# DNVT_box3.net
KiCad netlist of a schematic drawn in EAGLE
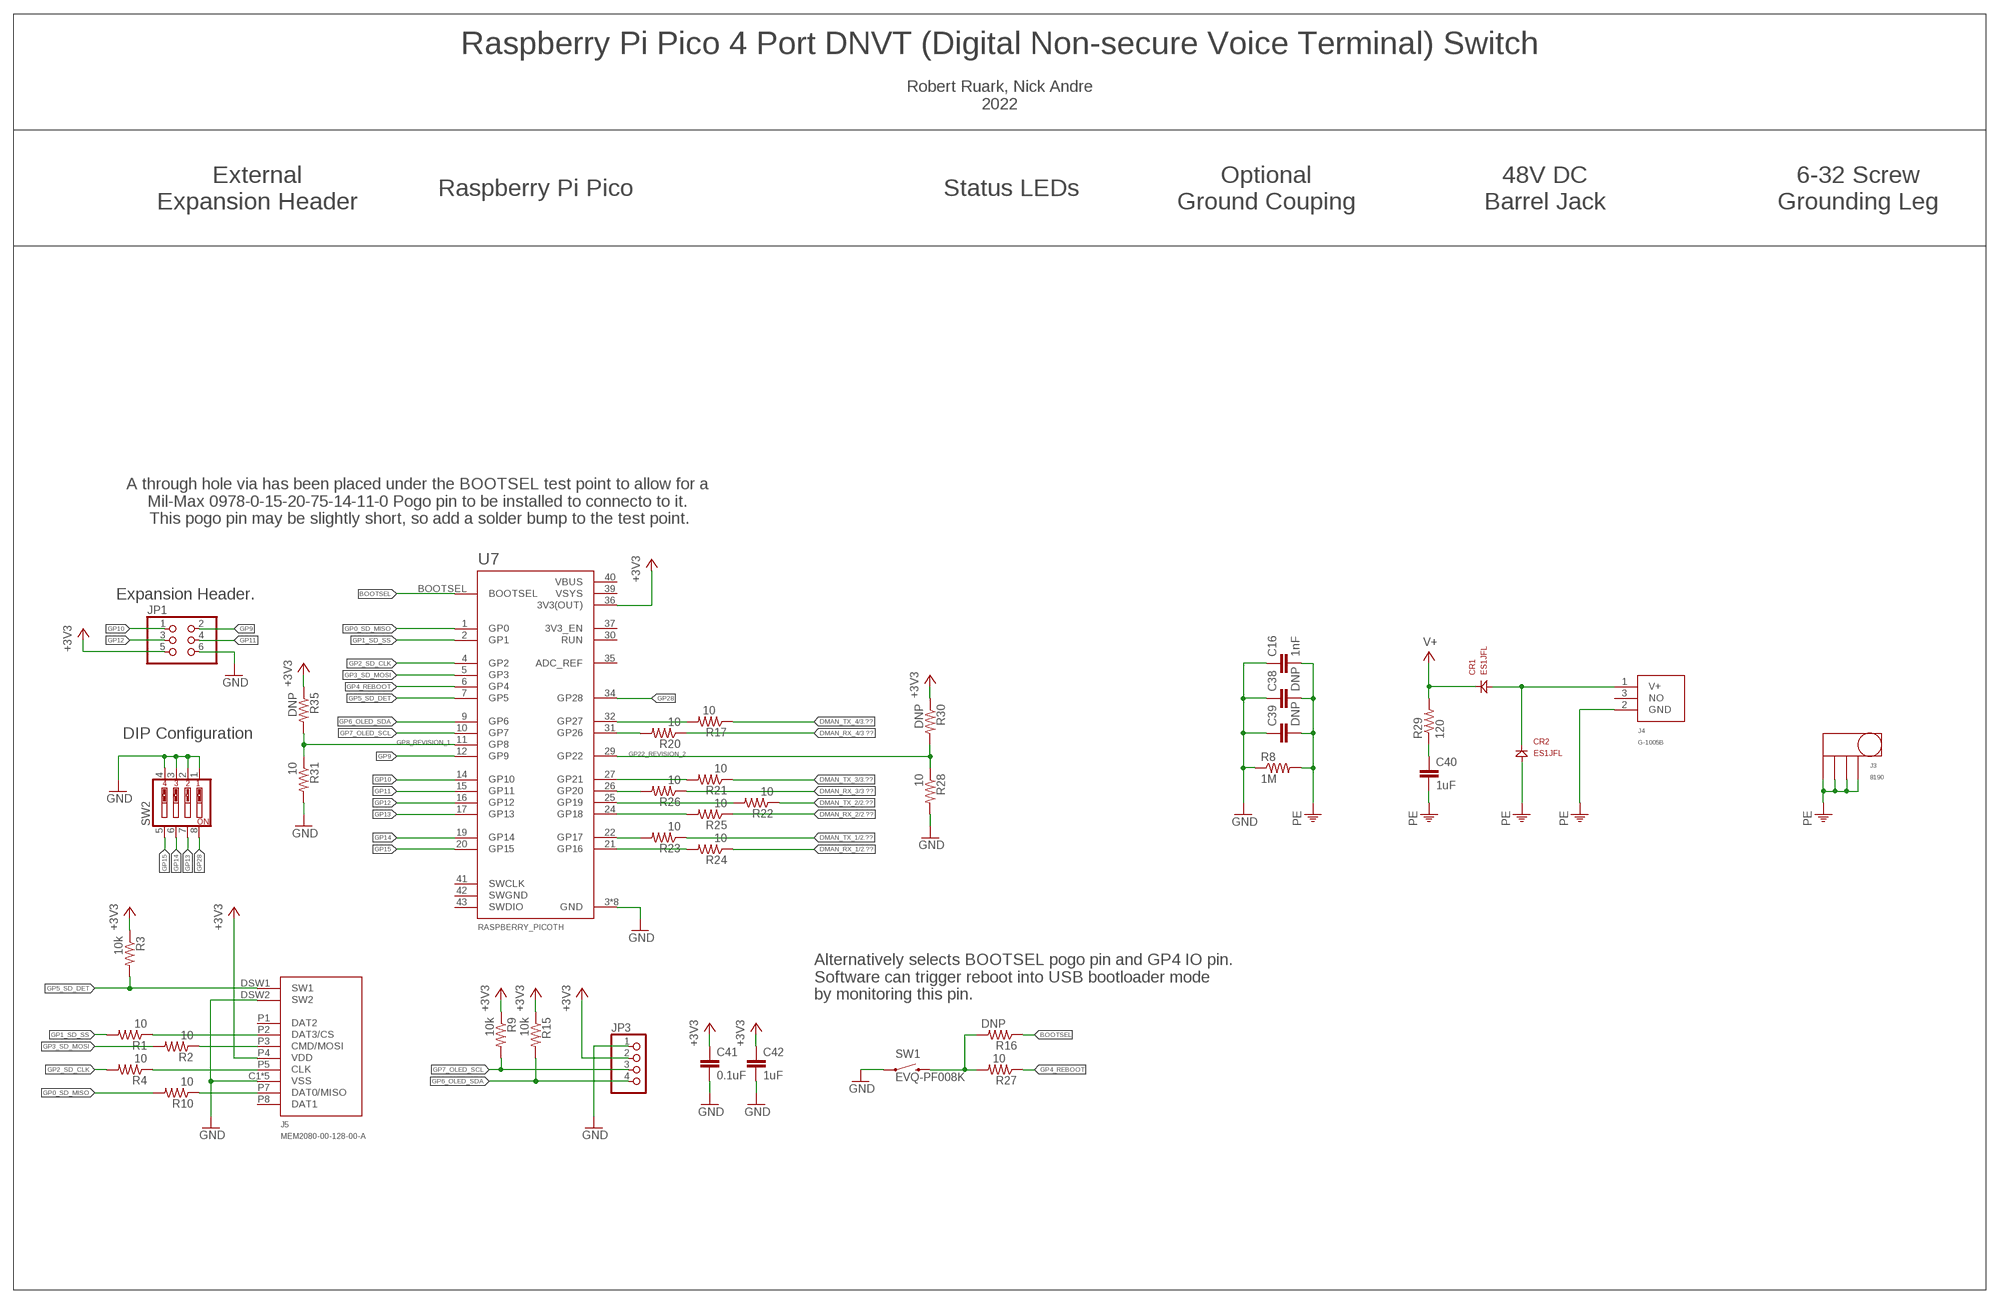
[diagram p0: schematic, sheet 1]
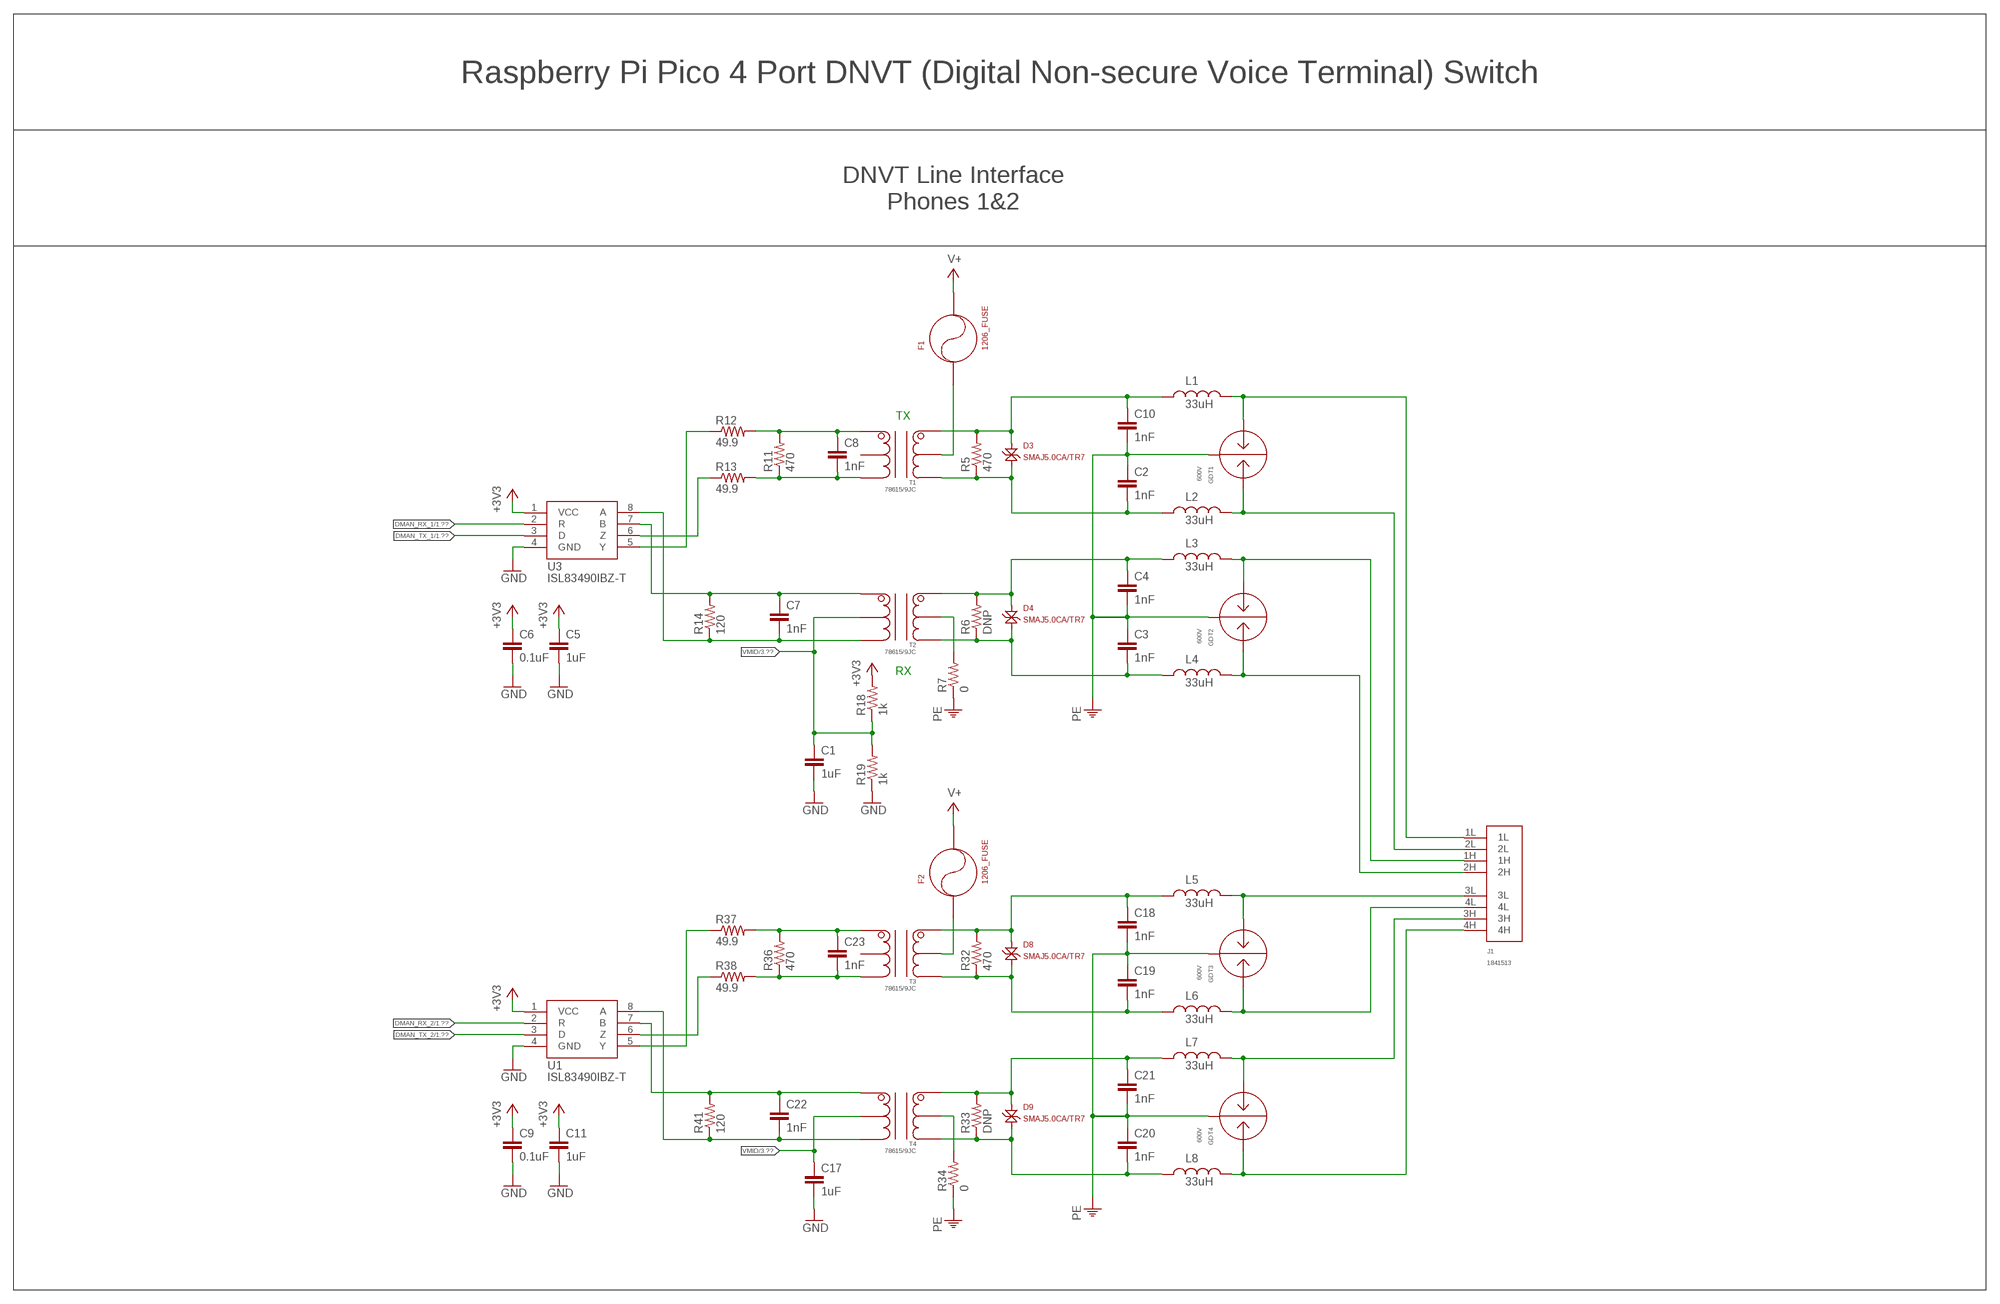
[diagram p1: schematic, sheet 2]
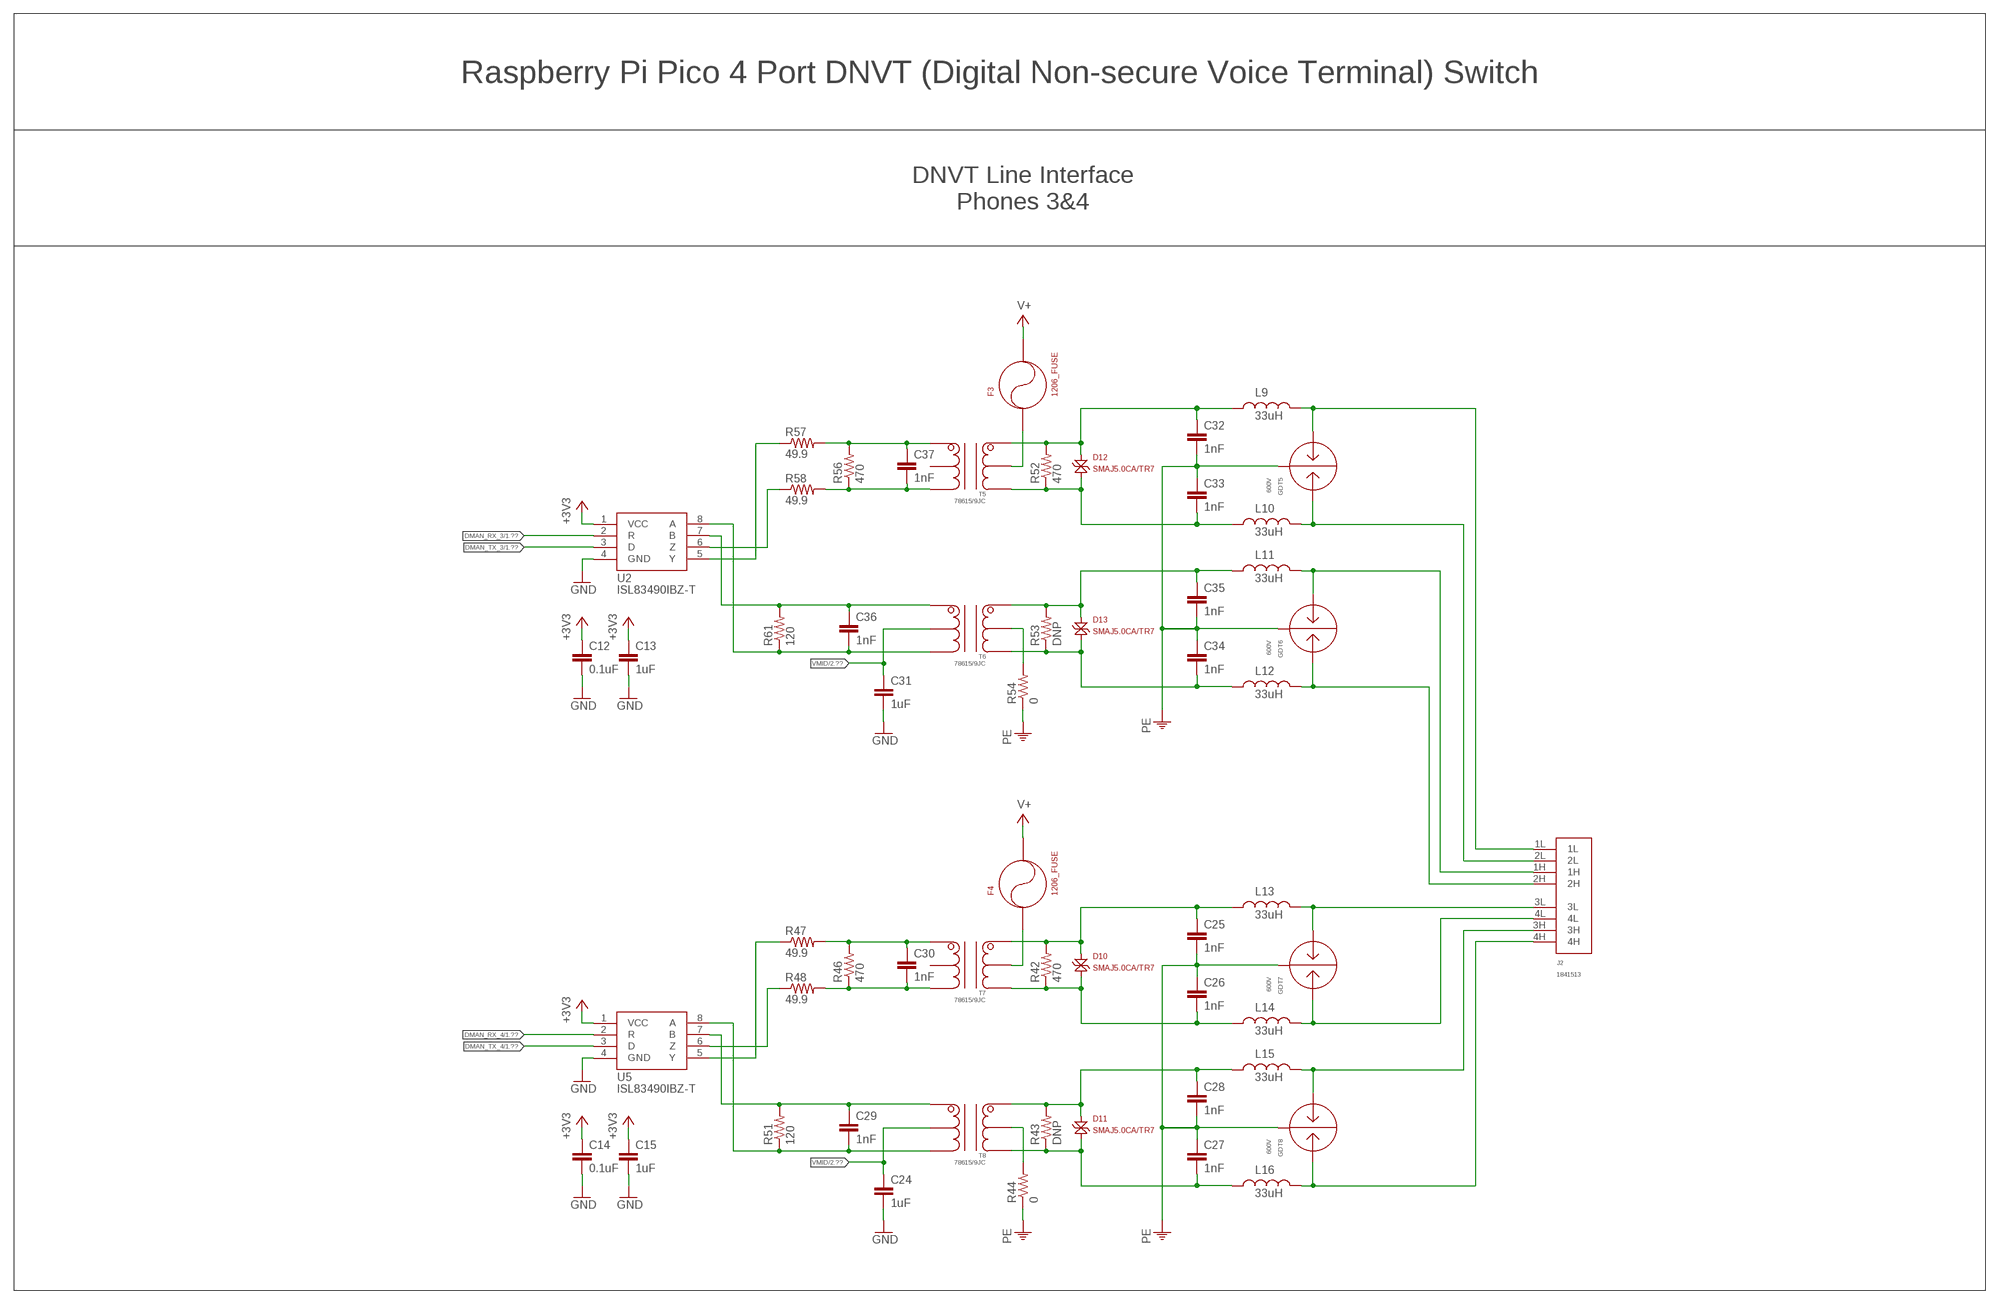
[diagram p2: schematic, sheet 3]

(export (version "E")
  (design (tool "Eeschema 10.0.6"))
  (components
    (comp (ref "C16")
      (value "1nF")
      (footprint "eagle-import:1206")
      (libsource (lib "eagle-import") (part "1206_CAPACITOR"))
    )
    (comp (ref "C38")
      (value "DNP")
      (footprint "eagle-import:1206")
      (libsource (lib "eagle-import") (part "1206_CAPACITOR"))
    )
    (comp (ref "C39")
      (value "DNP")
      (footprint "eagle-import:1206")
      (libsource (lib "eagle-import") (part "1206_CAPACITOR"))
    )
    (comp (ref "C40")
      (value "1uF")
      (footprint "eagle-import:1206")
      (libsource (lib "eagle-import") (part "1206_CAPACITOR"))
    )
    (comp (ref "C41")
      (value "0.1uF")
      (footprint "eagle-import:0603")
      (libsource (lib "eagle-import") (part "0603_CAPACITOR"))
    )
    (comp (ref "C42")
      (value "1uF")
      (footprint "eagle-import:0805")
      (libsource (lib "eagle-import") (part "0805_CAPACITOR"))
    )
    (comp (ref "CR1")
      (value "ES1JFL")
      (footprint "eagle-import:SOD123(AK)")
      (fields (field (name "PARTNO") "ES1JFLCT-ND"))
      (libsource (lib "eagle-import") (part "ES1JFL"))
    )
    (comp (ref "CR2")
      (value "ES1JFL")
      (footprint "eagle-import:SOD123(AK)")
      (fields (field (name "PARTNO") "ES1JFLCT-ND"))
      (libsource (lib "eagle-import") (part "ES1JFL"))
    )
    (comp (ref "J3")
      (value "8190")
      (footprint "eagle-import:7781")
      (fields (field (name "PARTNO") "36-8190-ND"))
      (libsource (lib "eagle-import") (part "8190"))
    )
    (comp (ref "J4")
      (value "G-1005B")
      (footprint "eagle-import:G-1005B")
      (fields (field (name "PARTNO") "1939-G-1005B-ND"))
      (libsource (lib "eagle-import") (part "G-1005B"))
    )
    (comp (ref "J5")
      (value "MEM2080-00-128-00-A")
      (footprint "eagle-import:MEM2080")
      (fields (field (name "PARTNO") "2073-MEM2080-00-128-00-ACT-ND"))
      (libsource (lib "eagle-import") (part "MEM2080-00-128-00-A"))
    )
    (comp (ref "JP1")
      (value "PINHD-2X3/90")
      (footprint "eagle-import:2X03_90")
      (libsource (lib "eagle-import") (part "PINHD-2X3/90"))
    )
    (comp (ref "JP3")
      (value "PINHD-1X4")
      (footprint "eagle-import:1X04")
      (libsource (lib "eagle-import") (part "PINHD-1X4"))
    )
    (comp (ref "R1")
      (value "10")
      (footprint "eagle-import:0603")
      (libsource (lib "eagle-import") (part "0603_RESISTOR"))
    )
    (comp (ref "R2")
      (value "10")
      (footprint "eagle-import:0603")
      (libsource (lib "eagle-import") (part "0603_RESISTOR"))
    )
    (comp (ref "R3")
      (value "10k")
      (footprint "eagle-import:0603")
      (libsource (lib "eagle-import") (part "0603_RESISTOR"))
    )
    (comp (ref "R4")
      (value "10")
      (footprint "eagle-import:0603")
      (libsource (lib "eagle-import") (part "0603_RESISTOR"))
    )
    (comp (ref "R8")
      (value "1M")
      (footprint "eagle-import:1206")
      (libsource (lib "eagle-import") (part "1206_RESISTOR"))
    )
    (comp (ref "R9")
      (value "10k")
      (footprint "eagle-import:0603")
      (libsource (lib "eagle-import") (part "0603_RESISTOR"))
    )
    (comp (ref "R10")
      (value "10")
      (footprint "eagle-import:0603")
      (libsource (lib "eagle-import") (part "0603_RESISTOR"))
    )
    (comp (ref "R15")
      (value "10k")
      (footprint "eagle-import:0603")
      (libsource (lib "eagle-import") (part "0603_RESISTOR"))
    )
    (comp (ref "R16")
      (value "DNP")
      (footprint "eagle-import:0603")
      (libsource (lib "eagle-import") (part "0603_RESISTOR"))
    )
    (comp (ref "R17")
      (value "10")
      (footprint "eagle-import:0603")
      (libsource (lib "eagle-import") (part "0603_RESISTOR"))
    )
    (comp (ref "R20")
      (value "10")
      (footprint "eagle-import:0603")
      (libsource (lib "eagle-import") (part "0603_RESISTOR"))
    )
    (comp (ref "R21")
      (value "10")
      (footprint "eagle-import:0603")
      (libsource (lib "eagle-import") (part "0603_RESISTOR"))
    )
    (comp (ref "R22")
      (value "10")
      (footprint "eagle-import:0603")
      (libsource (lib "eagle-import") (part "0603_RESISTOR"))
    )
    (comp (ref "R23")
      (value "10")
      (footprint "eagle-import:0603")
      (libsource (lib "eagle-import") (part "0603_RESISTOR"))
    )
    (comp (ref "R24")
      (value "10")
      (footprint "eagle-import:0603")
      (libsource (lib "eagle-import") (part "0603_RESISTOR"))
    )
    (comp (ref "R25")
      (value "10")
      (footprint "eagle-import:0603")
      (libsource (lib "eagle-import") (part "0603_RESISTOR"))
    )
    (comp (ref "R26")
      (value "10")
      (footprint "eagle-import:0603")
      (libsource (lib "eagle-import") (part "0603_RESISTOR"))
    )
    (comp (ref "R27")
      (value "10")
      (footprint "eagle-import:0603")
      (libsource (lib "eagle-import") (part "0603_RESISTOR"))
    )
    (comp (ref "R28")
      (value "10")
      (footprint "eagle-import:0603")
      (libsource (lib "eagle-import") (part "0603_RESISTOR"))
    )
    (comp (ref "R29")
      (value "120")
      (footprint "eagle-import:1206")
      (libsource (lib "eagle-import") (part "1206_RESISTOR"))
    )
    (comp (ref "R30")
      (value "DNP")
      (footprint "eagle-import:0603")
      (libsource (lib "eagle-import") (part "0603_RESISTOR"))
    )
    (comp (ref "R31")
      (value "10")
      (footprint "eagle-import:0603")
      (libsource (lib "eagle-import") (part "0603_RESISTOR"))
    )
    (comp (ref "R35")
      (value "DNP")
      (footprint "eagle-import:0603")
      (libsource (lib "eagle-import") (part "0603_RESISTOR"))
    )
    (comp (ref "SW1")
      (value "EVQ-PF008K")
      (footprint "eagle-import:EVQ-PF008K")
      (fields (field (name "PARTNO") "P10880S-ND"))
      (libsource (lib "eagle-import") (part "EVQ-PF008K"))
    )
    (comp (ref "SW2")
      (value "SW_DIP-4")
      (footprint "eagle-import:EDG-04")
      (libsource (lib "eagle-import") (part "SW_DIP-4"))
    )
    (comp (ref "U7")
      (value "RASPBERRY_PICOTH")
      (footprint "eagle-import:PICO-PKG-TH")
      (libsource (lib "eagle-import") (part "RASPBERRY_PICOTH"))
    )
    (comp (ref "C1")
      (value "1uF")
      (footprint "eagle-import:0805")
      (libsource (lib "eagle-import") (part "0805_CAPACITOR"))
    )
    (comp (ref "C2")
      (value "1nF")
      (footprint "eagle-import:0805")
      (libsource (lib "eagle-import") (part "0805_CAPACITOR"))
    )
    (comp (ref "C3")
      (value "1nF")
      (footprint "eagle-import:0805")
      (libsource (lib "eagle-import") (part "0805_CAPACITOR"))
    )
    (comp (ref "C4")
      (value "1nF")
      (footprint "eagle-import:0805")
      (libsource (lib "eagle-import") (part "0805_CAPACITOR"))
    )
    (comp (ref "C5")
      (value "1uF")
      (footprint "eagle-import:0805")
      (libsource (lib "eagle-import") (part "0805_CAPACITOR"))
    )
    (comp (ref "C6")
      (value "0.1uF")
      (footprint "eagle-import:0603")
      (libsource (lib "eagle-import") (part "0603_CAPACITOR"))
    )
    (comp (ref "C7")
      (value "1nF")
      (footprint "eagle-import:0805")
      (libsource (lib "eagle-import") (part "0805_CAPACITOR"))
    )
    (comp (ref "C8")
      (value "1nF")
      (footprint "eagle-import:0805")
      (libsource (lib "eagle-import") (part "0805_CAPACITOR"))
    )
    (comp (ref "C9")
      (value "0.1uF")
      (footprint "eagle-import:0603")
      (libsource (lib "eagle-import") (part "0603_CAPACITOR"))
    )
    (comp (ref "C10")
      (value "1nF")
      (footprint "eagle-import:0805")
      (libsource (lib "eagle-import") (part "0805_CAPACITOR"))
    )
    (comp (ref "C11")
      (value "1uF")
      (footprint "eagle-import:0805")
      (libsource (lib "eagle-import") (part "0805_CAPACITOR"))
    )
    (comp (ref "C17")
      (value "1uF")
      (footprint "eagle-import:0805")
      (libsource (lib "eagle-import") (part "0805_CAPACITOR"))
    )
    (comp (ref "C18")
      (value "1nF")
      (footprint "eagle-import:0805")
      (libsource (lib "eagle-import") (part "0805_CAPACITOR"))
    )
    (comp (ref "C19")
      (value "1nF")
      (footprint "eagle-import:0805")
      (libsource (lib "eagle-import") (part "0805_CAPACITOR"))
    )
    (comp (ref "C20")
      (value "1nF")
      (footprint "eagle-import:0805")
      (libsource (lib "eagle-import") (part "0805_CAPACITOR"))
    )
    (comp (ref "C21")
      (value "1nF")
      (footprint "eagle-import:0805")
      (libsource (lib "eagle-import") (part "0805_CAPACITOR"))
    )
    (comp (ref "C22")
      (value "1nF")
      (footprint "eagle-import:0805")
      (libsource (lib "eagle-import") (part "0805_CAPACITOR"))
    )
    (comp (ref "C23")
      (value "1nF")
      (footprint "eagle-import:0805")
      (libsource (lib "eagle-import") (part "0805_CAPACITOR"))
    )
    (comp (ref "D3")
      (value "SMAJ5.0CA/TR7")
      (footprint "eagle-import:DO-214AC_NO_POL")
      (libsource (lib "eagle-import") (part "SMAJ5.0CA/TR7"))
    )
    (comp (ref "D4")
      (value "SMAJ5.0CA/TR7")
      (footprint "eagle-import:DO-214AC_NO_POL")
      (libsource (lib "eagle-import") (part "SMAJ5.0CA/TR7"))
    )
    (comp (ref "D8")
      (value "SMAJ5.0CA/TR7")
      (footprint "eagle-import:DO-214AC_NO_POL")
      (libsource (lib "eagle-import") (part "SMAJ5.0CA/TR7"))
    )
    (comp (ref "D9")
      (value "SMAJ5.0CA/TR7")
      (footprint "eagle-import:DO-214AC_NO_POL")
      (libsource (lib "eagle-import") (part "SMAJ5.0CA/TR7"))
    )
    (comp (ref "F1")
      (value "1206_FUSE")
      (footprint "eagle-import:1206")
      (libsource (lib "eagle-import") (part "1206_FUSE"))
    )
    (comp (ref "F2")
      (value "1206_FUSE")
      (footprint "eagle-import:1206")
      (libsource (lib "eagle-import") (part "1206_FUSE"))
    )
    (comp (ref "GDT1")
      (value "600V")
      (footprint "eagle-import:2036_GDT")
      (fields (field (name "PARTNO") "2036-60-SM-RPLFCT-ND"))
      (libsource (lib "eagle-import") (part "2036-60-SM-RPLF"))
    )
    (comp (ref "GDT2")
      (value "600V")
      (footprint "eagle-import:2036_GDT")
      (fields (field (name "PARTNO") "2036-60-SM-RPLFCT-ND"))
      (libsource (lib "eagle-import") (part "2036-60-SM-RPLF"))
    )
    (comp (ref "GDT3")
      (value "600V")
      (footprint "eagle-import:2036_GDT")
      (fields (field (name "PARTNO") "2036-60-SM-RPLFCT-ND"))
      (libsource (lib "eagle-import") (part "2036-60-SM-RPLF"))
    )
    (comp (ref "GDT4")
      (value "600V")
      (footprint "eagle-import:2036_GDT")
      (fields (field (name "PARTNO") "2036-60-SM-RPLFCT-ND"))
      (libsource (lib "eagle-import") (part "2036-60-SM-RPLF"))
    )
    (comp (ref "J1")
      (value "1841513")
      (footprint "eagle-import:1841513")
      (fields (field (name "PARTNO") "277-10317-ND"))
      (libsource (lib "eagle-import") (part "1841513"))
    )
    (comp (ref "L1")
      (value "33uH")
      (footprint "eagle-import:SDR0403")
      (fields (field (name "PARTNO") "SDR0403-330KLCT-ND"))
      (libsource (lib "eagle-import") (part "SDR0403-330KL"))
    )
    (comp (ref "L2")
      (value "33uH")
      (footprint "eagle-import:SDR0403")
      (fields (field (name "PARTNO") "SDR0403-330KLCT-ND"))
      (libsource (lib "eagle-import") (part "SDR0403-330KL"))
    )
    (comp (ref "L3")
      (value "33uH")
      (footprint "eagle-import:SDR0403")
      (fields (field (name "PARTNO") "SDR0403-330KLCT-ND"))
      (libsource (lib "eagle-import") (part "SDR0403-330KL"))
    )
    (comp (ref "L4")
      (value "33uH")
      (footprint "eagle-import:SDR0403")
      (fields (field (name "PARTNO") "SDR0403-330KLCT-ND"))
      (libsource (lib "eagle-import") (part "SDR0403-330KL"))
    )
    (comp (ref "L5")
      (value "33uH")
      (footprint "eagle-import:SDR0403")
      (fields (field (name "PARTNO") "SDR0403-330KLCT-ND"))
      (libsource (lib "eagle-import") (part "SDR0403-330KL"))
    )
    (comp (ref "L6")
      (value "33uH")
      (footprint "eagle-import:SDR0403")
      (fields (field (name "PARTNO") "SDR0403-330KLCT-ND"))
      (libsource (lib "eagle-import") (part "SDR0403-330KL"))
    )
    (comp (ref "L7")
      (value "33uH")
      (footprint "eagle-import:SDR0403")
      (fields (field (name "PARTNO") "SDR0403-330KLCT-ND"))
      (libsource (lib "eagle-import") (part "SDR0403-330KL"))
    )
    (comp (ref "L8")
      (value "33uH")
      (footprint "eagle-import:SDR0403")
      (fields (field (name "PARTNO") "SDR0403-330KLCT-ND"))
      (libsource (lib "eagle-import") (part "SDR0403-330KL"))
    )
    (comp (ref "R5")
      (value "470")
      (footprint "eagle-import:R0805")
      (libsource (lib "eagle-import") (part "R-US_R0805"))
    )
    (comp (ref "R6")
      (value "DNP")
      (footprint "eagle-import:R0805")
      (libsource (lib "eagle-import") (part "R-US_R0805"))
    )
    (comp (ref "R7")
      (value "0")
      (footprint "eagle-import:R0805")
      (libsource (lib "eagle-import") (part "R-US_R0805"))
    )
    (comp (ref "R11")
      (value "470")
      (footprint "eagle-import:R0805")
      (libsource (lib "eagle-import") (part "R-US_R0805"))
    )
    (comp (ref "R12")
      (value "49.9")
      (footprint "eagle-import:R0805")
      (libsource (lib "eagle-import") (part "R-US_R0805"))
    )
    (comp (ref "R13")
      (value "49.9")
      (footprint "eagle-import:R0805")
      (libsource (lib "eagle-import") (part "R-US_R0805"))
    )
    (comp (ref "R14")
      (value "120")
      (footprint "eagle-import:1206")
      (libsource (lib "eagle-import") (part "1206_RESISTOR"))
    )
    (comp (ref "R18")
      (value "1k")
      (footprint "eagle-import:0603")
      (libsource (lib "eagle-import") (part "0603_RESISTOR"))
    )
    (comp (ref "R19")
      (value "1k")
      (footprint "eagle-import:0603")
      (libsource (lib "eagle-import") (part "0603_RESISTOR"))
    )
    (comp (ref "R32")
      (value "470")
      (footprint "eagle-import:R0805")
      (libsource (lib "eagle-import") (part "R-US_R0805"))
    )
    (comp (ref "R33")
      (value "DNP")
      (footprint "eagle-import:R0805")
      (libsource (lib "eagle-import") (part "R-US_R0805"))
    )
    (comp (ref "R34")
      (value "0")
      (footprint "eagle-import:R0805")
      (libsource (lib "eagle-import") (part "R-US_R0805"))
    )
    (comp (ref "R36")
      (value "470")
      (footprint "eagle-import:R0805")
      (libsource (lib "eagle-import") (part "R-US_R0805"))
    )
    (comp (ref "R37")
      (value "49.9")
      (footprint "eagle-import:R0805")
      (libsource (lib "eagle-import") (part "R-US_R0805"))
    )
    (comp (ref "R38")
      (value "49.9")
      (footprint "eagle-import:R0805")
      (libsource (lib "eagle-import") (part "R-US_R0805"))
    )
    (comp (ref "R41")
      (value "120")
      (footprint "eagle-import:1206")
      (libsource (lib "eagle-import") (part "1206_RESISTOR"))
    )
    (comp (ref "T1")
      (value "78615/9JC")
      (footprint "eagle-import:786")
      (fields (field (name "PARTNO") "811-2423-ND"))
      (libsource (lib "eagle-import") (part "78615/9JC"))
    )
    (comp (ref "T2")
      (value "78615/9JC")
      (footprint "eagle-import:786")
      (fields (field (name "PARTNO") "811-2423-ND"))
      (libsource (lib "eagle-import") (part "78615/9JC"))
    )
    (comp (ref "T3")
      (value "78615/9JC")
      (footprint "eagle-import:786")
      (fields (field (name "PARTNO") "811-2423-ND"))
      (libsource (lib "eagle-import") (part "78615/9JC"))
    )
    (comp (ref "T4")
      (value "78615/9JC")
      (footprint "eagle-import:786")
      (fields (field (name "PARTNO") "811-2423-ND"))
      (libsource (lib "eagle-import") (part "78615/9JC"))
    )
    (comp (ref "U1")
      (value "ISL83490IBZ-T")
      (footprint "eagle-import:SOIC8")
      (fields (field (name "PARTNO") "ISL83490IBZ-TCT-ND"))
      (libsource (lib "eagle-import") (part "ISL83490IBZ-T"))
    )
    (comp (ref "U3")
      (value "ISL83490IBZ-T")
      (footprint "eagle-import:SOIC8")
      (fields (field (name "PARTNO") "ISL83490IBZ-TCT-ND"))
      (libsource (lib "eagle-import") (part "ISL83490IBZ-T"))
    )
    (comp (ref "C12")
      (value "0.1uF")
      (footprint "eagle-import:0603")
      (libsource (lib "eagle-import") (part "0603_CAPACITOR"))
    )
    (comp (ref "C13")
      (value "1uF")
      (footprint "eagle-import:0805")
      (libsource (lib "eagle-import") (part "0805_CAPACITOR"))
    )
    (comp (ref "C14")
      (value "0.1uF")
      (footprint "eagle-import:0603")
      (libsource (lib "eagle-import") (part "0603_CAPACITOR"))
    )
    (comp (ref "C15")
      (value "1uF")
      (footprint "eagle-import:0805")
      (libsource (lib "eagle-import") (part "0805_CAPACITOR"))
    )
    (comp (ref "C24")
      (value "1uF")
      (footprint "eagle-import:0805")
      (libsource (lib "eagle-import") (part "0805_CAPACITOR"))
    )
    (comp (ref "C25")
      (value "1nF")
      (footprint "eagle-import:0805")
      (libsource (lib "eagle-import") (part "0805_CAPACITOR"))
    )
    (comp (ref "C26")
      (value "1nF")
      (footprint "eagle-import:0805")
      (libsource (lib "eagle-import") (part "0805_CAPACITOR"))
    )
    (comp (ref "C27")
      (value "1nF")
      (footprint "eagle-import:0805")
      (libsource (lib "eagle-import") (part "0805_CAPACITOR"))
    )
    (comp (ref "C28")
      (value "1nF")
      (footprint "eagle-import:0805")
      (libsource (lib "eagle-import") (part "0805_CAPACITOR"))
    )
    (comp (ref "C29")
      (value "1nF")
      (footprint "eagle-import:0805")
      (libsource (lib "eagle-import") (part "0805_CAPACITOR"))
    )
    (comp (ref "C30")
      (value "1nF")
      (footprint "eagle-import:0805")
      (libsource (lib "eagle-import") (part "0805_CAPACITOR"))
    )
    (comp (ref "C31")
      (value "1uF")
      (footprint "eagle-import:0805")
      (libsource (lib "eagle-import") (part "0805_CAPACITOR"))
    )
    (comp (ref "C32")
      (value "1nF")
      (footprint "eagle-import:0805")
      (libsource (lib "eagle-import") (part "0805_CAPACITOR"))
    )
    (comp (ref "C33")
      (value "1nF")
      (footprint "eagle-import:0805")
      (libsource (lib "eagle-import") (part "0805_CAPACITOR"))
    )
    (comp (ref "C34")
      (value "1nF")
      (footprint "eagle-import:0805")
      (libsource (lib "eagle-import") (part "0805_CAPACITOR"))
    )
    (comp (ref "C35")
      (value "1nF")
      (footprint "eagle-import:0805")
      (libsource (lib "eagle-import") (part "0805_CAPACITOR"))
    )
    (comp (ref "C36")
      (value "1nF")
      (footprint "eagle-import:0805")
      (libsource (lib "eagle-import") (part "0805_CAPACITOR"))
    )
    (comp (ref "C37")
      (value "1nF")
      (footprint "eagle-import:0805")
      (libsource (lib "eagle-import") (part "0805_CAPACITOR"))
    )
    (comp (ref "D10")
      (value "SMAJ5.0CA/TR7")
      (footprint "eagle-import:DO-214AC_NO_POL")
      (libsource (lib "eagle-import") (part "SMAJ5.0CA/TR7"))
    )
    (comp (ref "D11")
      (value "SMAJ5.0CA/TR7")
      (footprint "eagle-import:DO-214AC_NO_POL")
      (libsource (lib "eagle-import") (part "SMAJ5.0CA/TR7"))
    )
    (comp (ref "D12")
      (value "SMAJ5.0CA/TR7")
      (footprint "eagle-import:DO-214AC_NO_POL")
      (libsource (lib "eagle-import") (part "SMAJ5.0CA/TR7"))
    )
    (comp (ref "D13")
      (value "SMAJ5.0CA/TR7")
      (footprint "eagle-import:DO-214AC_NO_POL")
      (libsource (lib "eagle-import") (part "SMAJ5.0CA/TR7"))
    )
    (comp (ref "F3")
      (value "1206_FUSE")
      (footprint "eagle-import:1206")
      (libsource (lib "eagle-import") (part "1206_FUSE"))
    )
    (comp (ref "F4")
      (value "1206_FUSE")
      (footprint "eagle-import:1206")
      (libsource (lib "eagle-import") (part "1206_FUSE"))
    )
    (comp (ref "GDT5")
      (value "600V")
      (footprint "eagle-import:2036_GDT")
      (fields (field (name "PARTNO") "2036-60-SM-RPLFCT-ND"))
      (libsource (lib "eagle-import") (part "2036-60-SM-RPLF"))
    )
    (comp (ref "GDT6")
      (value "600V")
      (footprint "eagle-import:2036_GDT")
      (fields (field (name "PARTNO") "2036-60-SM-RPLFCT-ND"))
      (libsource (lib "eagle-import") (part "2036-60-SM-RPLF"))
    )
    (comp (ref "GDT7")
      (value "600V")
      (footprint "eagle-import:2036_GDT")
      (fields (field (name "PARTNO") "2036-60-SM-RPLFCT-ND"))
      (libsource (lib "eagle-import") (part "2036-60-SM-RPLF"))
    )
    (comp (ref "GDT8")
      (value "600V")
      (footprint "eagle-import:2036_GDT")
      (fields (field (name "PARTNO") "2036-60-SM-RPLFCT-ND"))
      (libsource (lib "eagle-import") (part "2036-60-SM-RPLF"))
    )
    (comp (ref "J2")
      (value "1841513")
      (footprint "eagle-import:1841513")
      (fields (field (name "PARTNO") "277-10317-ND"))
      (libsource (lib "eagle-import") (part "1841513"))
    )
    (comp (ref "L9")
      (value "33uH")
      (footprint "eagle-import:SDR0403")
      (fields (field (name "PARTNO") "SDR0403-330KLCT-ND"))
      (libsource (lib "eagle-import") (part "SDR0403-330KL"))
    )
    (comp (ref "L10")
      (value "33uH")
      (footprint "eagle-import:SDR0403")
      (fields (field (name "PARTNO") "SDR0403-330KLCT-ND"))
      (libsource (lib "eagle-import") (part "SDR0403-330KL"))
    )
    (comp (ref "L11")
      (value "33uH")
      (footprint "eagle-import:SDR0403")
      (fields (field (name "PARTNO") "SDR0403-330KLCT-ND"))
      (libsource (lib "eagle-import") (part "SDR0403-330KL"))
    )
    (comp (ref "L12")
      (value "33uH")
      (footprint "eagle-import:SDR0403")
      (fields (field (name "PARTNO") "SDR0403-330KLCT-ND"))
      (libsource (lib "eagle-import") (part "SDR0403-330KL"))
    )
    (comp (ref "L13")
      (value "33uH")
      (footprint "eagle-import:SDR0403")
      (fields (field (name "PARTNO") "SDR0403-330KLCT-ND"))
      (libsource (lib "eagle-import") (part "SDR0403-330KL"))
    )
    (comp (ref "L14")
      (value "33uH")
      (footprint "eagle-import:SDR0403")
      (fields (field (name "PARTNO") "SDR0403-330KLCT-ND"))
      (libsource (lib "eagle-import") (part "SDR0403-330KL"))
    )
    (comp (ref "L15")
      (value "33uH")
      (footprint "eagle-import:SDR0403")
      (fields (field (name "PARTNO") "SDR0403-330KLCT-ND"))
      (libsource (lib "eagle-import") (part "SDR0403-330KL"))
    )
    (comp (ref "L16")
      (value "33uH")
      (footprint "eagle-import:SDR0403")
      (fields (field (name "PARTNO") "SDR0403-330KLCT-ND"))
      (libsource (lib "eagle-import") (part "SDR0403-330KL"))
    )
    (comp (ref "R42")
      (value "470")
      (footprint "eagle-import:R0805")
      (libsource (lib "eagle-import") (part "R-US_R0805"))
    )
    (comp (ref "R43")
      (value "DNP")
      (footprint "eagle-import:R0805")
      (libsource (lib "eagle-import") (part "R-US_R0805"))
    )
    (comp (ref "R44")
      (value "0")
      (footprint "eagle-import:R0805")
      (libsource (lib "eagle-import") (part "R-US_R0805"))
    )
    (comp (ref "R46")
      (value "470")
      (footprint "eagle-import:R0805")
      (libsource (lib "eagle-import") (part "R-US_R0805"))
    )
    (comp (ref "R47")
      (value "49.9")
      (footprint "eagle-import:R0805")
      (libsource (lib "eagle-import") (part "R-US_R0805"))
    )
    (comp (ref "R48")
      (value "49.9")
      (footprint "eagle-import:R0805")
      (libsource (lib "eagle-import") (part "R-US_R0805"))
    )
    (comp (ref "R51")
      (value "120")
      (footprint "eagle-import:1206")
      (libsource (lib "eagle-import") (part "1206_RESISTOR"))
    )
    (comp (ref "R52")
      (value "470")
      (footprint "eagle-import:R0805")
      (libsource (lib "eagle-import") (part "R-US_R0805"))
    )
    (comp (ref "R53")
      (value "DNP")
      (footprint "eagle-import:R0805")
      (libsource (lib "eagle-import") (part "R-US_R0805"))
    )
    (comp (ref "R54")
      (value "0")
      (footprint "eagle-import:R0805")
      (libsource (lib "eagle-import") (part "R-US_R0805"))
    )
    (comp (ref "R56")
      (value "470")
      (footprint "eagle-import:R0805")
      (libsource (lib "eagle-import") (part "R-US_R0805"))
    )
    (comp (ref "R57")
      (value "49.9")
      (footprint "eagle-import:R0805")
      (libsource (lib "eagle-import") (part "R-US_R0805"))
    )
    (comp (ref "R58")
      (value "49.9")
      (footprint "eagle-import:R0805")
      (libsource (lib "eagle-import") (part "R-US_R0805"))
    )
    (comp (ref "R61")
      (value "120")
      (footprint "eagle-import:1206")
      (libsource (lib "eagle-import") (part "1206_RESISTOR"))
    )
    (comp (ref "T5")
      (value "78615/9JC")
      (footprint "eagle-import:786")
      (fields (field (name "PARTNO") "811-2423-ND"))
      (libsource (lib "eagle-import") (part "78615/9JC"))
    )
    (comp (ref "T6")
      (value "78615/9JC")
      (footprint "eagle-import:786")
      (fields (field (name "PARTNO") "811-2423-ND"))
      (libsource (lib "eagle-import") (part "78615/9JC"))
    )
    (comp (ref "T7")
      (value "78615/9JC")
      (footprint "eagle-import:786")
      (fields (field (name "PARTNO") "811-2423-ND"))
      (libsource (lib "eagle-import") (part "78615/9JC"))
    )
    (comp (ref "T8")
      (value "78615/9JC")
      (footprint "eagle-import:786")
      (fields (field (name "PARTNO") "811-2423-ND"))
      (libsource (lib "eagle-import") (part "78615/9JC"))
    )
    (comp (ref "U2")
      (value "ISL83490IBZ-T")
      (footprint "eagle-import:SOIC8")
      (fields (field (name "PARTNO") "ISL83490IBZ-TCT-ND"))
      (libsource (lib "eagle-import") (part "ISL83490IBZ-T"))
    )
    (comp (ref "U5")
      (value "ISL83490IBZ-T")
      (footprint "eagle-import:SOIC8")
      (fields (field (name "PARTNO") "ISL83490IBZ-TCT-ND"))
      (libsource (lib "eagle-import") (part "ISL83490IBZ-T"))
    )
  )
  (nets
    (net (code "1") (name "+3V3") (class "Default")
      (node (ref "C11") (pin "1") (pinfunction "1_1") (pintype "passive"))
      (node (ref "C12") (pin "1") (pinfunction "1_1") (pintype "passive"))
      (node (ref "C13") (pin "1") (pinfunction "1_1") (pintype "passive"))
      (node (ref "C14") (pin "1") (pinfunction "1_1") (pintype "passive"))
      (node (ref "C15") (pin "1") (pinfunction "1_1") (pintype "passive"))
      (node (ref "C41") (pin "1") (pinfunction "1_1") (pintype "passive"))
      (node (ref "C42") (pin "1") (pinfunction "1_1") (pintype "passive"))
      (node (ref "C5") (pin "1") (pinfunction "1_1") (pintype "passive"))
      (node (ref "C6") (pin "1") (pinfunction "1_1") (pintype "passive"))
      (node (ref "C9") (pin "1") (pinfunction "1_1") (pintype "passive"))
      (node (ref "J5") (pin "P4") (pinfunction "VDD_P4") (pintype "bidirectional"))
      (node (ref "JP1") (pin "5") (pinfunction "5_5") (pintype "passive"))
      (node (ref "JP3") (pin "2") (pinfunction "2_2") (pintype "passive"))
      (node (ref "R15") (pin "1") (pinfunction "1_1") (pintype "passive"))
      (node (ref "R18") (pin "2") (pinfunction "2_2") (pintype "passive"))
      (node (ref "R3") (pin "1") (pinfunction "1_1") (pintype "passive"))
      (node (ref "R30") (pin "1") (pinfunction "1_1") (pintype "passive"))
      (node (ref "R35") (pin "1") (pinfunction "1_1") (pintype "passive"))
      (node (ref "R9") (pin "1") (pinfunction "1_1") (pintype "passive"))
      (node (ref "U1") (pin "1") (pinfunction "VCC_1") (pintype "bidirectional"))
      (node (ref "U2") (pin "1") (pinfunction "VCC_1") (pintype "bidirectional"))
      (node (ref "U3") (pin "1") (pinfunction "VCC_1") (pintype "bidirectional"))
      (node (ref "U5") (pin "1") (pinfunction "VCC_1") (pintype "bidirectional"))
      (node (ref "U7") (pin "36") (pinfunction "3V3(OUT)_36") (pintype "power_in"))
    )
    (net (code "2") (name "BOOTSEL") (class "Default")
      (node (ref "R16") (pin "1") (pinfunction "1_1") (pintype "passive"))
      (node (ref "U7") (pin "BOOTSEL") (pinfunction "BOOTSEL_BOOTSEL") (pintype "bidirectional"))
    )
    (net (code "3") (name "DMAN_RX_1") (class "Default")
      (node (ref "R24") (pin "1") (pinfunction "1_1") (pintype "passive"))
      (node (ref "U3") (pin "2") (pinfunction "R_2") (pintype "bidirectional"))
    )
    (net (code "4") (name "DMAN_RX_2") (class "Default")
      (node (ref "R25") (pin "1") (pinfunction "1_1") (pintype "passive"))
      (node (ref "U1") (pin "2") (pinfunction "R_2") (pintype "bidirectional"))
    )
    (net (code "5") (name "DMAN_RX_3") (class "Default")
      (node (ref "R26") (pin "1") (pinfunction "1_1") (pintype "passive"))
      (node (ref "U2") (pin "2") (pinfunction "R_2") (pintype "bidirectional"))
    )
    (net (code "6") (name "DMAN_RX_4") (class "Default")
      (node (ref "R20") (pin "1") (pinfunction "1_1") (pintype "passive"))
      (node (ref "U5") (pin "2") (pinfunction "R_2") (pintype "bidirectional"))
    )
    (net (code "7") (name "DMAN_TX_1") (class "Default")
      (node (ref "R23") (pin "1") (pinfunction "1_1") (pintype "passive"))
      (node (ref "U3") (pin "3") (pinfunction "D_3") (pintype "bidirectional"))
    )
    (net (code "8") (name "DMAN_TX_2") (class "Default")
      (node (ref "R22") (pin "1") (pinfunction "1_1") (pintype "passive"))
      (node (ref "U1") (pin "3") (pinfunction "D_3") (pintype "bidirectional"))
    )
    (net (code "9") (name "DMAN_TX_3") (class "Default")
      (node (ref "R21") (pin "1") (pinfunction "1_1") (pintype "passive"))
      (node (ref "U2") (pin "3") (pinfunction "D_3") (pintype "bidirectional"))
    )
    (net (code "10") (name "DMAN_TX_4") (class "Default")
      (node (ref "R17") (pin "1") (pinfunction "1_1") (pintype "passive"))
      (node (ref "U5") (pin "3") (pinfunction "D_3") (pintype "bidirectional"))
    )
    (net (code "11") (name "GND") (class "Default")
      (node (ref "C1") (pin "2") (pinfunction "2_2") (pintype "passive"))
      (node (ref "C11") (pin "2") (pinfunction "2_2") (pintype "passive"))
      (node (ref "C12") (pin "2") (pinfunction "2_2") (pintype "passive"))
      (node (ref "C13") (pin "2") (pinfunction "2_2") (pintype "passive"))
      (node (ref "C14") (pin "2") (pinfunction "2_2") (pintype "passive"))
      (node (ref "C15") (pin "2") (pinfunction "2_2") (pintype "passive"))
      (node (ref "C16") (pin "1") (pinfunction "1_1") (pintype "passive"))
      (node (ref "C17") (pin "2") (pinfunction "2_2") (pintype "passive"))
      (node (ref "C24") (pin "2") (pinfunction "2_2") (pintype "passive"))
      (node (ref "C31") (pin "2") (pinfunction "2_2") (pintype "passive"))
      (node (ref "C38") (pin "1") (pinfunction "1_1") (pintype "passive"))
      (node (ref "C39") (pin "1") (pinfunction "1_1") (pintype "passive"))
      (node (ref "C41") (pin "2") (pinfunction "2_2") (pintype "passive"))
      (node (ref "C42") (pin "2") (pinfunction "2_2") (pintype "passive"))
      (node (ref "C5") (pin "2") (pinfunction "2_2") (pintype "passive"))
      (node (ref "C6") (pin "2") (pinfunction "2_2") (pintype "passive"))
      (node (ref "C9") (pin "2") (pinfunction "2_2") (pintype "passive"))
      (node (ref "J5") (pin "C1") (pinfunction "VSS_C1") (pintype "bidirectional"))
      (node (ref "J5") (pin "C2") (pinfunction "VSS_C2") (pintype "bidirectional"))
      (node (ref "J5") (pin "C3") (pinfunction "VSS_C3") (pintype "bidirectional"))
      (node (ref "J5") (pin "C4") (pinfunction "VSS_C4") (pintype "bidirectional"))
      (node (ref "J5") (pin "DSW2") (pinfunction "SW2_DSW2") (pintype "bidirectional"))
      (node (ref "J5") (pin "P6") (pinfunction "VSS_P6") (pintype "bidirectional"))
      (node (ref "JP1") (pin "6") (pinfunction "6_6") (pintype "passive"))
      (node (ref "JP3") (pin "1") (pinfunction "1_1") (pintype "passive"))
      (node (ref "R19") (pin "1") (pinfunction "1_1") (pintype "passive"))
      (node (ref "R28") (pin "2") (pinfunction "2_2") (pintype "passive"))
      (node (ref "R31") (pin "2") (pinfunction "2_2") (pintype "passive"))
      (node (ref "R8") (pin "1") (pinfunction "1_1") (pintype "passive"))
      (node (ref "SW1") (pin "S1") (pinfunction "1_S1") (pintype "passive"))
      (node (ref "SW2") (pin "1") (pinfunction "1_1") (pintype "passive"))
      (node (ref "SW2") (pin "2") (pinfunction "2_2") (pintype "passive"))
      (node (ref "SW2") (pin "3") (pinfunction "3_3") (pintype "passive"))
      (node (ref "SW2") (pin "4") (pinfunction "4_4") (pintype "passive"))
      (node (ref "U1") (pin "4") (pinfunction "GND_4") (pintype "bidirectional"))
      (node (ref "U2") (pin "4") (pinfunction "GND_4") (pintype "bidirectional"))
      (node (ref "U3") (pin "4") (pinfunction "GND_4") (pintype "bidirectional"))
      (node (ref "U5") (pin "4") (pinfunction "GND_4") (pintype "bidirectional"))
      (node (ref "U7") (pin "13") (pinfunction "GND_13") (pintype "power_in"))
      (node (ref "U7") (pin "18") (pinfunction "GND_18") (pintype "power_in"))
      (node (ref "U7") (pin "23") (pinfunction "GND_23") (pintype "power_in"))
      (node (ref "U7") (pin "28") (pinfunction "GND_28") (pintype "power_in"))
      (node (ref "U7") (pin "3") (pinfunction "GND_3") (pintype "power_in"))
      (node (ref "U7") (pin "33") (pinfunction "GND_33") (pintype "power_in"))
      (node (ref "U7") (pin "38") (pinfunction "GND_38") (pintype "power_in"))
      (node (ref "U7") (pin "8") (pinfunction "GND_8") (pintype "power_in"))
    )
    (net (code "12") (name "GP0_SD_MISO") (class "Default")
      (node (ref "R10") (pin "2") (pinfunction "2_2") (pintype "passive"))
      (node (ref "U7") (pin "1") (pinfunction "GP0_1") (pintype "bidirectional"))
    )
    (net (code "13") (name "GP1_SD_SS") (class "Default")
      (node (ref "R1") (pin "2") (pinfunction "2_2") (pintype "passive"))
      (node (ref "U7") (pin "2") (pinfunction "GP1_2") (pintype "bidirectional"))
    )
    (net (code "14") (name "GP2_SD_CLK") (class "Default")
      (node (ref "R4") (pin "2") (pinfunction "2_2") (pintype "passive"))
      (node (ref "U7") (pin "4") (pinfunction "GP2_4") (pintype "bidirectional"))
    )
    (net (code "15") (name "GP3_SD_MOSI") (class "Default")
      (node (ref "R2") (pin "2") (pinfunction "2_2") (pintype "passive"))
      (node (ref "U7") (pin "5") (pinfunction "GP3_5") (pintype "bidirectional"))
    )
    (net (code "16") (name "GP4_REBOOT") (class "Default")
      (node (ref "R27") (pin "1") (pinfunction "1_1") (pintype "passive"))
      (node (ref "U7") (pin "6") (pinfunction "GP4_6") (pintype "bidirectional"))
    )
    (net (code "17") (name "GP5_SD_DET") (class "Default")
      (node (ref "J5") (pin "DSW1") (pinfunction "SW1_DSW1") (pintype "bidirectional"))
      (node (ref "R3") (pin "2") (pinfunction "2_2") (pintype "passive"))
      (node (ref "U7") (pin "7") (pinfunction "GP5_7") (pintype "bidirectional"))
    )
    (net (code "18") (name "GP6_OLED_SDA") (class "Default")
      (node (ref "JP3") (pin "4") (pinfunction "4_4") (pintype "passive"))
      (node (ref "R15") (pin "2") (pinfunction "2_2") (pintype "passive"))
      (node (ref "U7") (pin "9") (pinfunction "GP6_9") (pintype "bidirectional"))
    )
    (net (code "19") (name "GP7_OLED_SCL") (class "Default")
      (node (ref "JP3") (pin "3") (pinfunction "3_3") (pintype "passive"))
      (node (ref "R9") (pin "2") (pinfunction "2_2") (pintype "passive"))
      (node (ref "U7") (pin "10") (pinfunction "GP7_10") (pintype "bidirectional"))
    )
    (net (code "20") (name "GP8_REVISION_1") (class "Default")
      (node (ref "R31") (pin "1") (pinfunction "1_1") (pintype "passive"))
      (node (ref "R35") (pin "2") (pinfunction "2_2") (pintype "passive"))
      (node (ref "U7") (pin "11") (pinfunction "GP8_11") (pintype "bidirectional"))
    )
    (net (code "21") (name "GP9") (class "Default")
      (node (ref "JP1") (pin "2") (pinfunction "2_2") (pintype "passive"))
      (node (ref "U7") (pin "12") (pinfunction "GP9_12") (pintype "bidirectional"))
    )
    (net (code "22") (name "GP10") (class "Default")
      (node (ref "JP1") (pin "1") (pinfunction "1_1") (pintype "passive"))
      (node (ref "U7") (pin "14") (pinfunction "GP10_14") (pintype "bidirectional"))
    )
    (net (code "23") (name "GP11") (class "Default")
      (node (ref "JP1") (pin "4") (pinfunction "4_4") (pintype "passive"))
      (node (ref "U7") (pin "15") (pinfunction "GP11_15") (pintype "bidirectional"))
    )
    (net (code "24") (name "GP12") (class "Default")
      (node (ref "JP1") (pin "3") (pinfunction "3_3") (pintype "passive"))
      (node (ref "U7") (pin "16") (pinfunction "GP12_16") (pintype "bidirectional"))
    )
    (net (code "25") (name "GP13") (class "Default")
      (node (ref "SW2") (pin "7") (pinfunction "7_7") (pintype "passive"))
      (node (ref "U7") (pin "17") (pinfunction "GP13_17") (pintype "bidirectional"))
    )
    (net (code "26") (name "GP14") (class "Default")
      (node (ref "SW2") (pin "6") (pinfunction "6_6") (pintype "passive"))
      (node (ref "U7") (pin "19") (pinfunction "GP14_19") (pintype "bidirectional"))
    )
    (net (code "27") (name "GP15") (class "Default")
      (node (ref "SW2") (pin "5") (pinfunction "5_5") (pintype "passive"))
      (node (ref "U7") (pin "20") (pinfunction "GP15_20") (pintype "bidirectional"))
    )
    (net (code "28") (name "GP22_REVISION_2") (class "Default")
      (node (ref "R28") (pin "1") (pinfunction "1_1") (pintype "passive"))
      (node (ref "R30") (pin "2") (pinfunction "2_2") (pintype "passive"))
      (node (ref "U7") (pin "29") (pinfunction "GP22_29") (pintype "bidirectional"))
    )
    (net (code "29") (name "GP28") (class "Default")
      (node (ref "SW2") (pin "8") (pinfunction "8_8") (pintype "passive"))
      (node (ref "U7") (pin "34") (pinfunction "GP28_34") (pintype "bidirectional"))
    )
    (net (code "30") (name "Net-(C8-Pad1)") (class "Default")
      (node (ref "C8") (pin "1") (pinfunction "1_1") (pintype "passive"))
      (node (ref "R11") (pin "2") (pinfunction "2_2") (pintype "passive"))
      (node (ref "R12") (pin "2") (pinfunction "2_2") (pintype "passive"))
      (node (ref "T1") (pin "6") (pinfunction "6_6") (pintype "bidirectional"))
    )
    (net (code "31") (name "Net-(C8-Pad2)") (class "Default")
      (node (ref "C8") (pin "2") (pinfunction "2_2") (pintype "passive"))
      (node (ref "R11") (pin "1") (pinfunction "1_1") (pintype "passive"))
      (node (ref "R13") (pin "2") (pinfunction "2_2") (pintype "passive"))
      (node (ref "T1") (pin "4") (pinfunction "4_4") (pintype "bidirectional"))
    )
    (net (code "32") (name "Net-(C23-Pad1)") (class "Default")
      (node (ref "C23") (pin "1") (pinfunction "1_1") (pintype "passive"))
      (node (ref "R36") (pin "2") (pinfunction "2_2") (pintype "passive"))
      (node (ref "R37") (pin "2") (pinfunction "2_2") (pintype "passive"))
      (node (ref "T3") (pin "6") (pinfunction "6_6") (pintype "bidirectional"))
    )
    (net (code "33") (name "Net-(C23-Pad2)") (class "Default")
      (node (ref "C23") (pin "2") (pinfunction "2_2") (pintype "passive"))
      (node (ref "R36") (pin "1") (pinfunction "1_1") (pintype "passive"))
      (node (ref "R38") (pin "2") (pinfunction "2_2") (pintype "passive"))
      (node (ref "T3") (pin "4") (pinfunction "4_4") (pintype "bidirectional"))
    )
    (net (code "34") (name "Net-(C30-Pad1)") (class "Default")
      (node (ref "C30") (pin "1") (pinfunction "1_1") (pintype "passive"))
      (node (ref "R46") (pin "2") (pinfunction "2_2") (pintype "passive"))
      (node (ref "R47") (pin "2") (pinfunction "2_2") (pintype "passive"))
      (node (ref "T7") (pin "6") (pinfunction "6_6") (pintype "bidirectional"))
    )
    (net (code "35") (name "Net-(C30-Pad2)") (class "Default")
      (node (ref "C30") (pin "2") (pinfunction "2_2") (pintype "passive"))
      (node (ref "R46") (pin "1") (pinfunction "1_1") (pintype "passive"))
      (node (ref "R48") (pin "2") (pinfunction "2_2") (pintype "passive"))
      (node (ref "T7") (pin "4") (pinfunction "4_4") (pintype "bidirectional"))
    )
    (net (code "36") (name "Net-(C37-Pad1)") (class "Default")
      (node (ref "C37") (pin "1") (pinfunction "1_1") (pintype "passive"))
      (node (ref "R56") (pin "2") (pinfunction "2_2") (pintype "passive"))
      (node (ref "R57") (pin "2") (pinfunction "2_2") (pintype "passive"))
      (node (ref "T5") (pin "6") (pinfunction "6_6") (pintype "bidirectional"))
    )
    (net (code "37") (name "Net-(C37-Pad2)") (class "Default")
      (node (ref "C37") (pin "2") (pinfunction "2_2") (pintype "passive"))
      (node (ref "R56") (pin "1") (pinfunction "1_1") (pintype "passive"))
      (node (ref "R58") (pin "2") (pinfunction "2_2") (pintype "passive"))
      (node (ref "T5") (pin "4") (pinfunction "4_4") (pintype "bidirectional"))
    )
    (net (code "38") (name "Net-(C40-Pad1)") (class "Default")
      (node (ref "C40") (pin "1") (pinfunction "1_1") (pintype "passive"))
      (node (ref "R29") (pin "1") (pinfunction "1_1") (pintype "passive"))
    )
    (net (code "39") (name "Net-(D3-K)") (class "Default")
      (node (ref "C10") (pin "1") (pinfunction "1_1") (pintype "passive"))
      (node (ref "D3") (pin "C") (pinfunction "K_C") (pintype "bidirectional"))
      (node (ref "L1") (pin "1") (pinfunction "P$1_1") (pintype "bidirectional"))
      (node (ref "R5") (pin "2") (pinfunction "2_2") (pintype "passive"))
      (node (ref "T1") (pin "1") (pinfunction "1_1") (pintype "bidirectional"))
    )
    (net (code "40") (name "Net-(D4-K)") (class "Default")
      (node (ref "C4") (pin "1") (pinfunction "1_1") (pintype "passive"))
      (node (ref "D4") (pin "C") (pinfunction "K_C") (pintype "bidirectional"))
      (node (ref "L3") (pin "1") (pinfunction "P$1_1") (pintype "bidirectional"))
      (node (ref "R6") (pin "2") (pinfunction "2_2") (pintype "passive"))
      (node (ref "T2") (pin "1") (pinfunction "1_1") (pintype "bidirectional"))
    )
    (net (code "41") (name "Net-(D8-K)") (class "Default")
      (node (ref "C18") (pin "1") (pinfunction "1_1") (pintype "passive"))
      (node (ref "D8") (pin "C") (pinfunction "K_C") (pintype "bidirectional"))
      (node (ref "L5") (pin "1") (pinfunction "P$1_1") (pintype "bidirectional"))
      (node (ref "R32") (pin "2") (pinfunction "2_2") (pintype "passive"))
      (node (ref "T3") (pin "1") (pinfunction "1_1") (pintype "bidirectional"))
    )
    (net (code "42") (name "Net-(D9-K)") (class "Default")
      (node (ref "C21") (pin "1") (pinfunction "1_1") (pintype "passive"))
      (node (ref "D9") (pin "C") (pinfunction "K_C") (pintype "bidirectional"))
      (node (ref "L7") (pin "1") (pinfunction "P$1_1") (pintype "bidirectional"))
      (node (ref "R33") (pin "2") (pinfunction "2_2") (pintype "passive"))
      (node (ref "T4") (pin "1") (pinfunction "1_1") (pintype "bidirectional"))
    )
    (net (code "43") (name "Net-(D10-K)") (class "Default")
      (node (ref "C25") (pin "1") (pinfunction "1_1") (pintype "passive"))
      (node (ref "D10") (pin "C") (pinfunction "K_C") (pintype "bidirectional"))
      (node (ref "L13") (pin "1") (pinfunction "P$1_1") (pintype "bidirectional"))
      (node (ref "R42") (pin "2") (pinfunction "2_2") (pintype "passive"))
      (node (ref "T7") (pin "1") (pinfunction "1_1") (pintype "bidirectional"))
    )
    (net (code "44") (name "Net-(D11-K)") (class "Default")
      (node (ref "C28") (pin "1") (pinfunction "1_1") (pintype "passive"))
      (node (ref "D11") (pin "C") (pinfunction "K_C") (pintype "bidirectional"))
      (node (ref "L15") (pin "1") (pinfunction "P$1_1") (pintype "bidirectional"))
      (node (ref "R43") (pin "2") (pinfunction "2_2") (pintype "passive"))
      (node (ref "T8") (pin "1") (pinfunction "1_1") (pintype "bidirectional"))
    )
    (net (code "45") (name "Net-(D12-K)") (class "Default")
      (node (ref "C32") (pin "1") (pinfunction "1_1") (pintype "passive"))
      (node (ref "D12") (pin "C") (pinfunction "K_C") (pintype "bidirectional"))
      (node (ref "L9") (pin "1") (pinfunction "P$1_1") (pintype "bidirectional"))
      (node (ref "R52") (pin "2") (pinfunction "2_2") (pintype "passive"))
      (node (ref "T5") (pin "1") (pinfunction "1_1") (pintype "bidirectional"))
    )
    (net (code "46") (name "Net-(D13-K)") (class "Default")
      (node (ref "C35") (pin "1") (pinfunction "1_1") (pintype "passive"))
      (node (ref "D13") (pin "C") (pinfunction "K_C") (pintype "bidirectional"))
      (node (ref "L11") (pin "1") (pinfunction "P$1_1") (pintype "bidirectional"))
      (node (ref "R53") (pin "2") (pinfunction "2_2") (pintype "passive"))
      (node (ref "T6") (pin "1") (pinfunction "1_1") (pintype "bidirectional"))
    )
    (net (code "47") (name "Net-(F1-P$1)") (class "Default")
      (node (ref "F1") (pin "1") (pinfunction "P$1_1") (pintype "bidirectional"))
      (node (ref "T1") (pin "2") (pinfunction "2_2") (pintype "bidirectional"))
    )
    (net (code "48") (name "Net-(F2-P$1)") (class "Default")
      (node (ref "F2") (pin "1") (pinfunction "P$1_1") (pintype "bidirectional"))
      (node (ref "T3") (pin "2") (pinfunction "2_2") (pintype "bidirectional"))
    )
    (net (code "49") (name "Net-(F3-P$1)") (class "Default")
      (node (ref "F3") (pin "1") (pinfunction "P$1_1") (pintype "bidirectional"))
      (node (ref "T5") (pin "2") (pinfunction "2_2") (pintype "bidirectional"))
    )
    (net (code "50") (name "Net-(F4-P$1)") (class "Default")
      (node (ref "F4") (pin "1") (pinfunction "P$1_1") (pintype "bidirectional"))
      (node (ref "T7") (pin "2") (pinfunction "2_2") (pintype "bidirectional"))
    )
    (net (code "51") (name "Net-(J4-V+)") (class "Default")
      (node (ref "CR1") (pin "A") (pinfunction "A_A") (pintype "bidirectional"))
      (node (ref "CR2") (pin "K") (pinfunction "K_K") (pintype "bidirectional"))
      (node (ref "J4") (pin "1") (pinfunction "V+_1") (pintype "bidirectional"))
    )
    (net (code "52") (name "Net-(J5-CLK)") (class "Default")
      (node (ref "J5") (pin "P5") (pinfunction "CLK_P5") (pintype "bidirectional"))
      (node (ref "R4") (pin "1") (pinfunction "1_1") (pintype "passive"))
    )
    (net (code "53") (name "Net-(J5-CMD{slash}MOSI)") (class "Default")
      (node (ref "J5") (pin "P3") (pinfunction "CMD/MOSI_P3") (pintype "bidirectional"))
      (node (ref "R2") (pin "1") (pinfunction "1_1") (pintype "passive"))
    )
    (net (code "54") (name "Net-(J5-DAT0{slash}MISO)") (class "Default")
      (node (ref "J5") (pin "P7") (pinfunction "DAT0/MISO_P7") (pintype "bidirectional"))
      (node (ref "R10") (pin "1") (pinfunction "1_1") (pintype "passive"))
    )
    (net (code "55") (name "Net-(J5-DAT3{slash}CS)") (class "Default")
      (node (ref "J5") (pin "P2") (pinfunction "DAT3/CS_P2") (pintype "bidirectional"))
      (node (ref "R1") (pin "1") (pinfunction "1_1") (pintype "passive"))
    )
    (net (code "56") (name "Net-(L1-P$2)") (class "Default")
      (node (ref "GDT1") (pin "L1") (pinfunction "L1_L1") (pintype "bidirectional"))
      (node (ref "J1") (pin "1L") (pinfunction "1L_1L") (pintype "bidirectional"))
      (node (ref "L1") (pin "2") (pinfunction "P$2_2") (pintype "bidirectional"))
    )
    (net (code "57") (name "Net-(L2-P$1)") (class "Default")
      (node (ref "C2") (pin "2") (pinfunction "2_2") (pintype "passive"))
      (node (ref "D3") (pin "A") (pinfunction "A_A") (pintype "bidirectional"))
      (node (ref "L2") (pin "1") (pinfunction "P$1_1") (pintype "bidirectional"))
      (node (ref "R5") (pin "1") (pinfunction "1_1") (pintype "passive"))
      (node (ref "T1") (pin "3") (pinfunction "3_3") (pintype "bidirectional"))
    )
    (net (code "58") (name "Net-(L2-P$2)") (class "Default")
      (node (ref "GDT1") (pin "L2") (pinfunction "L2_L2") (pintype "bidirectional"))
      (node (ref "J1") (pin "2L") (pinfunction "2L_2L") (pintype "bidirectional"))
      (node (ref "L2") (pin "2") (pinfunction "P$2_2") (pintype "bidirectional"))
    )
    (net (code "59") (name "Net-(L3-P$2)") (class "Default")
      (node (ref "GDT2") (pin "L1") (pinfunction "L1_L1") (pintype "bidirectional"))
      (node (ref "J1") (pin "1H") (pinfunction "1H_1H") (pintype "bidirectional"))
      (node (ref "L3") (pin "2") (pinfunction "P$2_2") (pintype "bidirectional"))
    )
    (net (code "60") (name "Net-(L4-P$1)") (class "Default")
      (node (ref "C3") (pin "2") (pinfunction "2_2") (pintype "passive"))
      (node (ref "D4") (pin "A") (pinfunction "A_A") (pintype "bidirectional"))
      (node (ref "L4") (pin "1") (pinfunction "P$1_1") (pintype "bidirectional"))
      (node (ref "R6") (pin "1") (pinfunction "1_1") (pintype "passive"))
      (node (ref "T2") (pin "3") (pinfunction "3_3") (pintype "bidirectional"))
    )
    (net (code "61") (name "Net-(L4-P$2)") (class "Default")
      (node (ref "GDT2") (pin "L2") (pinfunction "L2_L2") (pintype "bidirectional"))
      (node (ref "J1") (pin "2H") (pinfunction "2H_2H") (pintype "bidirectional"))
      (node (ref "L4") (pin "2") (pinfunction "P$2_2") (pintype "bidirectional"))
    )
    (net (code "62") (name "Net-(L5-P$2)") (class "Default")
      (node (ref "GDT3") (pin "L1") (pinfunction "L1_L1") (pintype "bidirectional"))
      (node (ref "J1") (pin "3L") (pinfunction "3L_3L") (pintype "bidirectional"))
      (node (ref "L5") (pin "2") (pinfunction "P$2_2") (pintype "bidirectional"))
    )
    (net (code "63") (name "Net-(L6-P$1)") (class "Default")
      (node (ref "C19") (pin "2") (pinfunction "2_2") (pintype "passive"))
      (node (ref "D8") (pin "A") (pinfunction "A_A") (pintype "bidirectional"))
      (node (ref "L6") (pin "1") (pinfunction "P$1_1") (pintype "bidirectional"))
      (node (ref "R32") (pin "1") (pinfunction "1_1") (pintype "passive"))
      (node (ref "T3") (pin "3") (pinfunction "3_3") (pintype "bidirectional"))
    )
    (net (code "64") (name "Net-(L6-P$2)") (class "Default")
      (node (ref "GDT3") (pin "L2") (pinfunction "L2_L2") (pintype "bidirectional"))
      (node (ref "J1") (pin "4L") (pinfunction "4L_4L") (pintype "bidirectional"))
      (node (ref "L6") (pin "2") (pinfunction "P$2_2") (pintype "bidirectional"))
    )
    (net (code "65") (name "Net-(L7-P$2)") (class "Default")
      (node (ref "GDT4") (pin "L1") (pinfunction "L1_L1") (pintype "bidirectional"))
      (node (ref "J1") (pin "3H") (pinfunction "3H_3H") (pintype "bidirectional"))
      (node (ref "L7") (pin "2") (pinfunction "P$2_2") (pintype "bidirectional"))
    )
    (net (code "66") (name "Net-(L8-P$1)") (class "Default")
      (node (ref "C20") (pin "2") (pinfunction "2_2") (pintype "passive"))
      (node (ref "D9") (pin "A") (pinfunction "A_A") (pintype "bidirectional"))
      (node (ref "L8") (pin "1") (pinfunction "P$1_1") (pintype "bidirectional"))
      (node (ref "R33") (pin "1") (pinfunction "1_1") (pintype "passive"))
      (node (ref "T4") (pin "3") (pinfunction "3_3") (pintype "bidirectional"))
    )
    (net (code "67") (name "Net-(L8-P$2)") (class "Default")
      (node (ref "GDT4") (pin "L2") (pinfunction "L2_L2") (pintype "bidirectional"))
      (node (ref "J1") (pin "4H") (pinfunction "4H_4H") (pintype "bidirectional"))
      (node (ref "L8") (pin "2") (pinfunction "P$2_2") (pintype "bidirectional"))
    )
    (net (code "68") (name "Net-(L9-P$2)") (class "Default")
      (node (ref "GDT5") (pin "L1") (pinfunction "L1_L1") (pintype "bidirectional"))
      (node (ref "J2") (pin "1L") (pinfunction "1L_1L") (pintype "bidirectional"))
      (node (ref "L9") (pin "2") (pinfunction "P$2_2") (pintype "bidirectional"))
    )
    (net (code "69") (name "Net-(L10-P$1)") (class "Default")
      (node (ref "C33") (pin "2") (pinfunction "2_2") (pintype "passive"))
      (node (ref "D12") (pin "A") (pinfunction "A_A") (pintype "bidirectional"))
      (node (ref "L10") (pin "1") (pinfunction "P$1_1") (pintype "bidirectional"))
      (node (ref "R52") (pin "1") (pinfunction "1_1") (pintype "passive"))
      (node (ref "T5") (pin "3") (pinfunction "3_3") (pintype "bidirectional"))
    )
    (net (code "70") (name "Net-(L10-P$2)") (class "Default")
      (node (ref "GDT5") (pin "L2") (pinfunction "L2_L2") (pintype "bidirectional"))
      (node (ref "J2") (pin "2L") (pinfunction "2L_2L") (pintype "bidirectional"))
      (node (ref "L10") (pin "2") (pinfunction "P$2_2") (pintype "bidirectional"))
    )
    (net (code "71") (name "Net-(L11-P$2)") (class "Default")
      (node (ref "GDT6") (pin "L1") (pinfunction "L1_L1") (pintype "bidirectional"))
      (node (ref "J2") (pin "1H") (pinfunction "1H_1H") (pintype "bidirectional"))
      (node (ref "L11") (pin "2") (pinfunction "P$2_2") (pintype "bidirectional"))
    )
    (net (code "72") (name "Net-(L12-P$1)") (class "Default")
      (node (ref "C34") (pin "2") (pinfunction "2_2") (pintype "passive"))
      (node (ref "D13") (pin "A") (pinfunction "A_A") (pintype "bidirectional"))
      (node (ref "L12") (pin "1") (pinfunction "P$1_1") (pintype "bidirectional"))
      (node (ref "R53") (pin "1") (pinfunction "1_1") (pintype "passive"))
      (node (ref "T6") (pin "3") (pinfunction "3_3") (pintype "bidirectional"))
    )
    (net (code "73") (name "Net-(L12-P$2)") (class "Default")
      (node (ref "GDT6") (pin "L2") (pinfunction "L2_L2") (pintype "bidirectional"))
      (node (ref "J2") (pin "2H") (pinfunction "2H_2H") (pintype "bidirectional"))
      (node (ref "L12") (pin "2") (pinfunction "P$2_2") (pintype "bidirectional"))
    )
    (net (code "74") (name "Net-(L13-P$2)") (class "Default")
      (node (ref "GDT7") (pin "L1") (pinfunction "L1_L1") (pintype "bidirectional"))
      (node (ref "J2") (pin "3L") (pinfunction "3L_3L") (pintype "bidirectional"))
      (node (ref "L13") (pin "2") (pinfunction "P$2_2") (pintype "bidirectional"))
    )
    (net (code "75") (name "Net-(L14-P$1)") (class "Default")
      (node (ref "C26") (pin "2") (pinfunction "2_2") (pintype "passive"))
      (node (ref "D10") (pin "A") (pinfunction "A_A") (pintype "bidirectional"))
      (node (ref "L14") (pin "1") (pinfunction "P$1_1") (pintype "bidirectional"))
      (node (ref "R42") (pin "1") (pinfunction "1_1") (pintype "passive"))
      (node (ref "T7") (pin "3") (pinfunction "3_3") (pintype "bidirectional"))
    )
    (net (code "76") (name "Net-(L14-P$2)") (class "Default")
      (node (ref "GDT7") (pin "L2") (pinfunction "L2_L2") (pintype "bidirectional"))
      (node (ref "J2") (pin "4L") (pinfunction "4L_4L") (pintype "bidirectional"))
      (node (ref "L14") (pin "2") (pinfunction "P$2_2") (pintype "bidirectional"))
    )
    (net (code "77") (name "Net-(L15-P$2)") (class "Default")
      (node (ref "GDT8") (pin "L1") (pinfunction "L1_L1") (pintype "bidirectional"))
      (node (ref "J2") (pin "3H") (pinfunction "3H_3H") (pintype "bidirectional"))
      (node (ref "L15") (pin "2") (pinfunction "P$2_2") (pintype "bidirectional"))
    )
    (net (code "78") (name "Net-(L16-P$1)") (class "Default")
      (node (ref "C27") (pin "2") (pinfunction "2_2") (pintype "passive"))
      (node (ref "D11") (pin "A") (pinfunction "A_A") (pintype "bidirectional"))
      (node (ref "L16") (pin "1") (pinfunction "P$1_1") (pintype "bidirectional"))
      (node (ref "R43") (pin "1") (pinfunction "1_1") (pintype "passive"))
      (node (ref "T8") (pin "3") (pinfunction "3_3") (pintype "bidirectional"))
    )
    (net (code "79") (name "Net-(L16-P$2)") (class "Default")
      (node (ref "GDT8") (pin "L2") (pinfunction "L2_L2") (pintype "bidirectional"))
      (node (ref "J2") (pin "4H") (pinfunction "4H_4H") (pintype "bidirectional"))
      (node (ref "L16") (pin "2") (pinfunction "P$2_2") (pintype "bidirectional"))
    )
    (net (code "80") (name "Net-(R7-Pad2)") (class "Default")
      (node (ref "R7") (pin "2") (pinfunction "2_2") (pintype "passive"))
      (node (ref "T2") (pin "2") (pinfunction "2_2") (pintype "bidirectional"))
    )
    (net (code "81") (name "Net-(R34-Pad2)") (class "Default")
      (node (ref "R34") (pin "2") (pinfunction "2_2") (pintype "passive"))
      (node (ref "T4") (pin "2") (pinfunction "2_2") (pintype "bidirectional"))
    )
    (net (code "82") (name "Net-(R44-Pad2)") (class "Default")
      (node (ref "R44") (pin "2") (pinfunction "2_2") (pintype "passive"))
      (node (ref "T8") (pin "2") (pinfunction "2_2") (pintype "bidirectional"))
    )
    (net (code "83") (name "Net-(R54-Pad2)") (class "Default")
      (node (ref "R54") (pin "2") (pinfunction "2_2") (pintype "passive"))
      (node (ref "T6") (pin "2") (pinfunction "2_2") (pintype "bidirectional"))
    )
    (net (code "84") (name "Net-(SW1-2)") (class "Default")
      (node (ref "R16") (pin "2") (pinfunction "2_2") (pintype "passive"))
      (node (ref "R27") (pin "2") (pinfunction "2_2") (pintype "passive"))
      (node (ref "SW1") (pin "S2") (pinfunction "2_S2") (pintype "passive"))
    )
    (net (code "85") (name "Net-(U1-A)") (class "Default")
      (node (ref "C22") (pin "2") (pinfunction "2_2") (pintype "passive"))
      (node (ref "R41") (pin "1") (pinfunction "1_1") (pintype "passive"))
      (node (ref "T4") (pin "4") (pinfunction "4_4") (pintype "bidirectional"))
      (node (ref "U1") (pin "8") (pinfunction "A_8") (pintype "bidirectional"))
    )
    (net (code "86") (name "Net-(U1-B)") (class "Default")
      (node (ref "C22") (pin "1") (pinfunction "1_1") (pintype "passive"))
      (node (ref "R41") (pin "2") (pinfunction "2_2") (pintype "passive"))
      (node (ref "T4") (pin "6") (pinfunction "6_6") (pintype "bidirectional"))
      (node (ref "U1") (pin "7") (pinfunction "B_7") (pintype "bidirectional"))
    )
    (net (code "87") (name "Net-(U1-Y)") (class "Default")
      (node (ref "R37") (pin "1") (pinfunction "1_1") (pintype "passive"))
      (node (ref "U1") (pin "5") (pinfunction "Y_5") (pintype "bidirectional"))
    )
    (net (code "88") (name "Net-(U1-Z)") (class "Default")
      (node (ref "R38") (pin "1") (pinfunction "1_1") (pintype "passive"))
      (node (ref "U1") (pin "6") (pinfunction "Z_6") (pintype "bidirectional"))
    )
    (net (code "89") (name "Net-(U2-A)") (class "Default")
      (node (ref "C36") (pin "2") (pinfunction "2_2") (pintype "passive"))
      (node (ref "R61") (pin "1") (pinfunction "1_1") (pintype "passive"))
      (node (ref "T6") (pin "4") (pinfunction "4_4") (pintype "bidirectional"))
      (node (ref "U2") (pin "8") (pinfunction "A_8") (pintype "bidirectional"))
    )
    (net (code "90") (name "Net-(U2-B)") (class "Default")
      (node (ref "C36") (pin "1") (pinfunction "1_1") (pintype "passive"))
      (node (ref "R61") (pin "2") (pinfunction "2_2") (pintype "passive"))
      (node (ref "T6") (pin "6") (pinfunction "6_6") (pintype "bidirectional"))
      (node (ref "U2") (pin "7") (pinfunction "B_7") (pintype "bidirectional"))
    )
    (net (code "91") (name "Net-(U2-Y)") (class "Default")
      (node (ref "R57") (pin "1") (pinfunction "1_1") (pintype "passive"))
      (node (ref "U2") (pin "5") (pinfunction "Y_5") (pintype "bidirectional"))
    )
    (net (code "92") (name "Net-(U2-Z)") (class "Default")
      (node (ref "R58") (pin "1") (pinfunction "1_1") (pintype "passive"))
      (node (ref "U2") (pin "6") (pinfunction "Z_6") (pintype "bidirectional"))
    )
    (net (code "93") (name "Net-(U3-A)") (class "Default")
      (node (ref "C7") (pin "2") (pinfunction "2_2") (pintype "passive"))
      (node (ref "R14") (pin "1") (pinfunction "1_1") (pintype "passive"))
      (node (ref "T2") (pin "4") (pinfunction "4_4") (pintype "bidirectional"))
      (node (ref "U3") (pin "8") (pinfunction "A_8") (pintype "bidirectional"))
    )
    (net (code "94") (name "Net-(U3-B)") (class "Default")
      (node (ref "C7") (pin "1") (pinfunction "1_1") (pintype "passive"))
      (node (ref "R14") (pin "2") (pinfunction "2_2") (pintype "passive"))
      (node (ref "T2") (pin "6") (pinfunction "6_6") (pintype "bidirectional"))
      (node (ref "U3") (pin "7") (pinfunction "B_7") (pintype "bidirectional"))
    )
    (net (code "95") (name "Net-(U3-Y)") (class "Default")
      (node (ref "R12") (pin "1") (pinfunction "1_1") (pintype "passive"))
      (node (ref "U3") (pin "5") (pinfunction "Y_5") (pintype "bidirectional"))
    )
    (net (code "96") (name "Net-(U3-Z)") (class "Default")
      (node (ref "R13") (pin "1") (pinfunction "1_1") (pintype "passive"))
      (node (ref "U3") (pin "6") (pinfunction "Z_6") (pintype "bidirectional"))
    )
    (net (code "97") (name "Net-(U5-A)") (class "Default")
      (node (ref "C29") (pin "2") (pinfunction "2_2") (pintype "passive"))
      (node (ref "R51") (pin "1") (pinfunction "1_1") (pintype "passive"))
      (node (ref "T8") (pin "4") (pinfunction "4_4") (pintype "bidirectional"))
      (node (ref "U5") (pin "8") (pinfunction "A_8") (pintype "bidirectional"))
    )
    (net (code "98") (name "Net-(U5-B)") (class "Default")
      (node (ref "C29") (pin "1") (pinfunction "1_1") (pintype "passive"))
      (node (ref "R51") (pin "2") (pinfunction "2_2") (pintype "passive"))
      (node (ref "T8") (pin "6") (pinfunction "6_6") (pintype "bidirectional"))
      (node (ref "U5") (pin "7") (pinfunction "B_7") (pintype "bidirectional"))
    )
    (net (code "99") (name "Net-(U5-Y)") (class "Default")
      (node (ref "R47") (pin "1") (pinfunction "1_1") (pintype "passive"))
      (node (ref "U5") (pin "5") (pinfunction "Y_5") (pintype "bidirectional"))
    )
    (net (code "100") (name "Net-(U5-Z)") (class "Default")
      (node (ref "R48") (pin "1") (pinfunction "1_1") (pintype "passive"))
      (node (ref "U5") (pin "6") (pinfunction "Z_6") (pintype "bidirectional"))
    )
    (net (code "101") (name "Net-(U7-GP16)") (class "Default")
      (node (ref "R24") (pin "2") (pinfunction "2_2") (pintype "passive"))
      (node (ref "U7") (pin "21") (pinfunction "GP16_21") (pintype "bidirectional"))
    )
    (net (code "102") (name "Net-(U7-GP17)") (class "Default")
      (node (ref "R23") (pin "2") (pinfunction "2_2") (pintype "passive"))
      (node (ref "U7") (pin "22") (pinfunction "GP17_22") (pintype "bidirectional"))
    )
    (net (code "103") (name "Net-(U7-GP18)") (class "Default")
      (node (ref "R25") (pin "2") (pinfunction "2_2") (pintype "passive"))
      (node (ref "U7") (pin "24") (pinfunction "GP18_24") (pintype "bidirectional"))
    )
    (net (code "104") (name "Net-(U7-GP19)") (class "Default")
      (node (ref "R22") (pin "2") (pinfunction "2_2") (pintype "passive"))
      (node (ref "U7") (pin "25") (pinfunction "GP19_25") (pintype "bidirectional"))
    )
    (net (code "105") (name "Net-(U7-GP20)") (class "Default")
      (node (ref "R26") (pin "2") (pinfunction "2_2") (pintype "passive"))
      (node (ref "U7") (pin "26") (pinfunction "GP20_26") (pintype "bidirectional"))
    )
    (net (code "106") (name "Net-(U7-GP21)") (class "Default")
      (node (ref "R21") (pin "2") (pinfunction "2_2") (pintype "passive"))
      (node (ref "U7") (pin "27") (pinfunction "GP21_27") (pintype "bidirectional"))
    )
    (net (code "107") (name "Net-(U7-GP26)") (class "Default")
      (node (ref "R20") (pin "2") (pinfunction "2_2") (pintype "passive"))
      (node (ref "U7") (pin "31") (pinfunction "GP26_31") (pintype "bidirectional"))
    )
    (net (code "108") (name "Net-(U7-GP27)") (class "Default")
      (node (ref "R17") (pin "2") (pinfunction "2_2") (pintype "passive"))
      (node (ref "U7") (pin "32") (pinfunction "GP27_32") (pintype "bidirectional"))
    )
    (net (code "109") (name "PE") (class "Default")
      (node (ref "C10") (pin "2") (pinfunction "2_2") (pintype "passive"))
      (node (ref "C16") (pin "2") (pinfunction "2_2") (pintype "passive"))
      (node (ref "C18") (pin "2") (pinfunction "2_2") (pintype "passive"))
      (node (ref "C19") (pin "1") (pinfunction "1_1") (pintype "passive"))
      (node (ref "C2") (pin "1") (pinfunction "1_1") (pintype "passive"))
      (node (ref "C20") (pin "1") (pinfunction "1_1") (pintype "passive"))
      (node (ref "C21") (pin "2") (pinfunction "2_2") (pintype "passive"))
      (node (ref "C25") (pin "2") (pinfunction "2_2") (pintype "passive"))
      (node (ref "C26") (pin "1") (pinfunction "1_1") (pintype "passive"))
      (node (ref "C27") (pin "1") (pinfunction "1_1") (pintype "passive"))
      (node (ref "C28") (pin "2") (pinfunction "2_2") (pintype "passive"))
      (node (ref "C3") (pin "1") (pinfunction "1_1") (pintype "passive"))
      (node (ref "C32") (pin "2") (pinfunction "2_2") (pintype "passive"))
      (node (ref "C33") (pin "1") (pinfunction "1_1") (pintype "passive"))
      (node (ref "C34") (pin "1") (pinfunction "1_1") (pintype "passive"))
      (node (ref "C35") (pin "2") (pinfunction "2_2") (pintype "passive"))
      (node (ref "C38") (pin "2") (pinfunction "2_2") (pintype "passive"))
      (node (ref "C39") (pin "2") (pinfunction "2_2") (pintype "passive"))
      (node (ref "C4") (pin "2") (pinfunction "2_2") (pintype "passive"))
      (node (ref "C40") (pin "2") (pinfunction "2_2") (pintype "passive"))
      (node (ref "CR2") (pin "A") (pinfunction "A_A") (pintype "bidirectional"))
      (node (ref "GDT1") (pin "C") (pinfunction "C_C") (pintype "bidirectional"))
      (node (ref "GDT2") (pin "C") (pinfunction "C_C") (pintype "bidirectional"))
      (node (ref "GDT3") (pin "C") (pinfunction "C_C") (pintype "bidirectional"))
      (node (ref "GDT4") (pin "C") (pinfunction "C_C") (pintype "bidirectional"))
      (node (ref "GDT5") (pin "C") (pinfunction "C_C") (pintype "bidirectional"))
      (node (ref "GDT6") (pin "C") (pinfunction "C_C") (pintype "bidirectional"))
      (node (ref "GDT7") (pin "C") (pinfunction "C_C") (pintype "bidirectional"))
      (node (ref "GDT8") (pin "C") (pinfunction "C_C") (pintype "bidirectional"))
      (node (ref "J3") (pin "P$1") (pinfunction "P$1_P$1") (pintype "bidirectional"))
      (node (ref "J3") (pin "P$2") (pinfunction "P$2_P$2") (pintype "bidirectional"))
      (node (ref "J3") (pin "P$3") (pinfunction "P$3_P$3") (pintype "bidirectional"))
      (node (ref "J3") (pin "P$4") (pinfunction "P$4_P$4") (pintype "bidirectional"))
      (node (ref "J4") (pin "2") (pinfunction "GND_2") (pintype "bidirectional"))
      (node (ref "R34") (pin "1") (pinfunction "1_1") (pintype "passive"))
      (node (ref "R44") (pin "1") (pinfunction "1_1") (pintype "passive"))
      (node (ref "R54") (pin "1") (pinfunction "1_1") (pintype "passive"))
      (node (ref "R7") (pin "1") (pinfunction "1_1") (pintype "passive"))
      (node (ref "R8") (pin "2") (pinfunction "2_2") (pintype "passive"))
    )
    (net (code "110") (name "SWGND") (class "Default")
      (node (ref "U7") (pin "42") (pinfunction "SWGND_42") (pintype "power_in"))
    )
    (net (code "111") (name "V+") (class "Default")
      (node (ref "CR1") (pin "K") (pinfunction "K_K") (pintype "bidirectional"))
      (node (ref "F1") (pin "2") (pinfunction "P$2_2") (pintype "bidirectional"))
      (node (ref "F2") (pin "2") (pinfunction "P$2_2") (pintype "bidirectional"))
      (node (ref "F3") (pin "2") (pinfunction "P$2_2") (pintype "bidirectional"))
      (node (ref "F4") (pin "2") (pinfunction "P$2_2") (pintype "bidirectional"))
      (node (ref "R29") (pin "2") (pinfunction "2_2") (pintype "passive"))
    )
    (net (code "112") (name "VBUS") (class "Default")
      (node (ref "U7") (pin "40") (pinfunction "VBUS_40") (pintype "power_in"))
    )
    (net (code "113") (name "VMID") (class "Default")
      (node (ref "C1") (pin "1") (pinfunction "1_1") (pintype "passive"))
      (node (ref "C17") (pin "1") (pinfunction "1_1") (pintype "passive"))
      (node (ref "C24") (pin "1") (pinfunction "1_1") (pintype "passive"))
      (node (ref "C31") (pin "1") (pinfunction "1_1") (pintype "passive"))
      (node (ref "R18") (pin "1") (pinfunction "1_1") (pintype "passive"))
      (node (ref "R19") (pin "2") (pinfunction "2_2") (pintype "passive"))
      (node (ref "T2") (pin "5") (pinfunction "5_5") (pintype "bidirectional"))
      (node (ref "T4") (pin "5") (pinfunction "5_5") (pintype "bidirectional"))
      (node (ref "T6") (pin "5") (pinfunction "5_5") (pintype "bidirectional"))
      (node (ref "T8") (pin "5") (pinfunction "5_5") (pintype "bidirectional"))
    )
    (net (code "114") (name "VSYS") (class "Default")
      (node (ref "U7") (pin "39") (pinfunction "VSYS_39") (pintype "power_in"))
    )
    (net (code "115") (name "unconnected-(J4-NO-Pad3)") (class "Default")
      (node (ref "J4") (pin "3") (pinfunction "NO_3") (pintype "bidirectional"))
    )
    (net (code "116") (name "unconnected-(J5-DAT1-PadP8)") (class "Default")
      (node (ref "J5") (pin "P8") (pinfunction "DAT1_P8") (pintype "bidirectional"))
    )
    (net (code "117") (name "unconnected-(J5-DAT2-PadP1)") (class "Default")
      (node (ref "J5") (pin "P1") (pinfunction "DAT2_P1") (pintype "bidirectional"))
    )
    (net (code "118") (name "unconnected-(T1-Pad5)") (class "Default")
      (node (ref "T1") (pin "5") (pinfunction "5_5") (pintype "bidirectional"))
    )
    (net (code "119") (name "unconnected-(T3-Pad5)") (class "Default")
      (node (ref "T3") (pin "5") (pinfunction "5_5") (pintype "bidirectional"))
    )
    (net (code "120") (name "unconnected-(T5-Pad5)") (class "Default")
      (node (ref "T5") (pin "5") (pinfunction "5_5") (pintype "bidirectional"))
    )
    (net (code "121") (name "unconnected-(T7-Pad5)") (class "Default")
      (node (ref "T7") (pin "5") (pinfunction "5_5") (pintype "bidirectional"))
    )
    (net (code "122") (name "unconnected-(U7-3V3_EN-Pad37)") (class "Default")
      (node (ref "U7") (pin "37") (pinfunction "3V3_EN_37") (pintype "input"))
    )
    (net (code "123") (name "unconnected-(U7-ADC_REF-Pad35)") (class "Default")
      (node (ref "U7") (pin "35") (pinfunction "ADC_REF_35") (pintype "input"))
    )
    (net (code "124") (name "unconnected-(U7-RUN-Pad30)") (class "Default")
      (node (ref "U7") (pin "30") (pinfunction "RUN_30") (pintype "input"))
    )
    (net (code "125") (name "unconnected-(U7-SWCLK-Pad41)") (class "Default")
      (node (ref "U7") (pin "41") (pinfunction "SWCLK_41") (pintype "input"))
    )
    (net (code "126") (name "unconnected-(U7-SWDIO-Pad43)") (class "Default")
      (node (ref "U7") (pin "43") (pinfunction "SWDIO_43") (pintype "bidirectional"))
    )
  )
)
